# RASPILOTv1_1.net
KiCad netlist of a schematic drawn in EAGLE
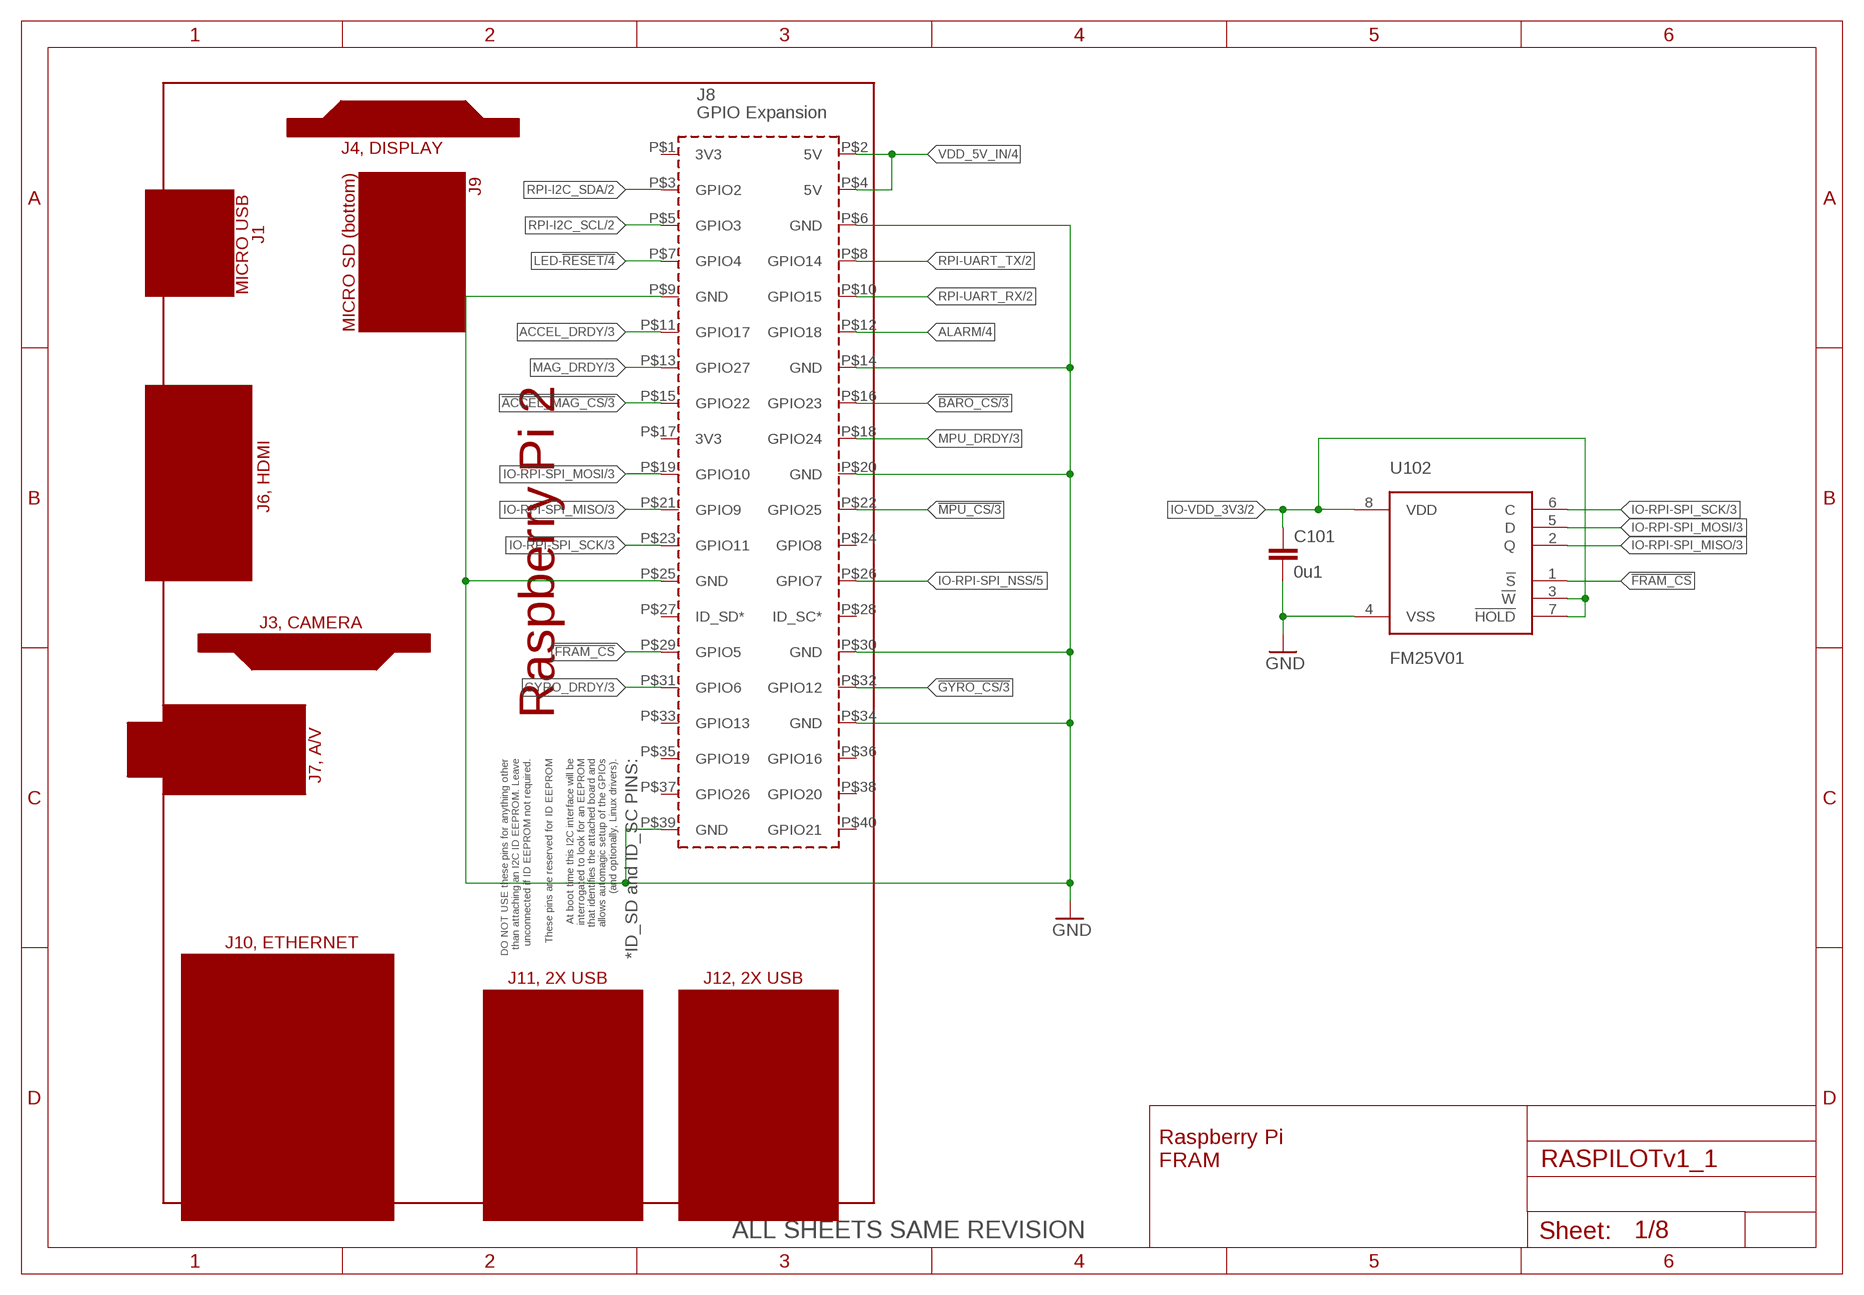
[diagram p0: schematic, sheet 1]
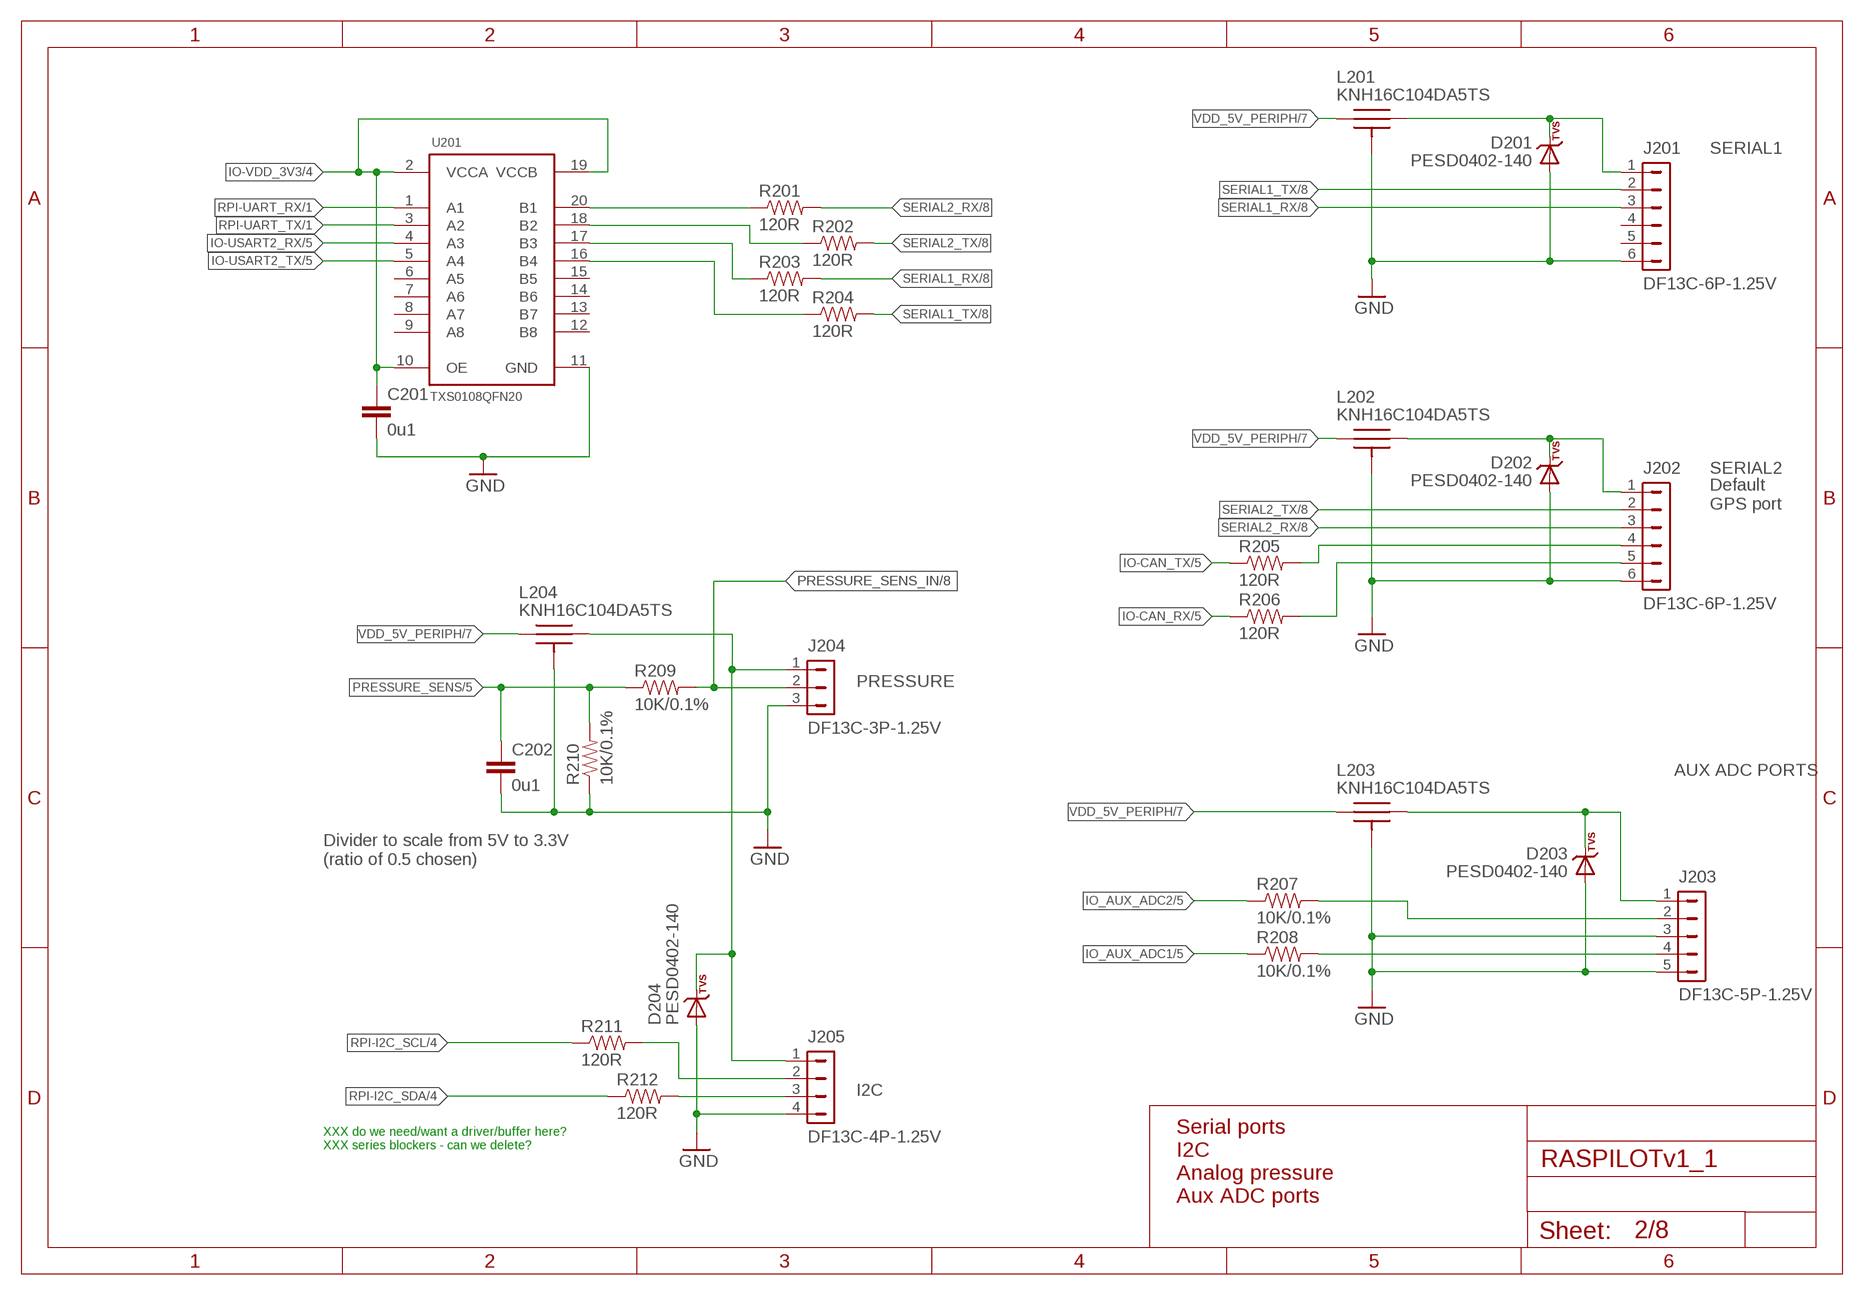
[diagram p1: schematic, sheet 2]
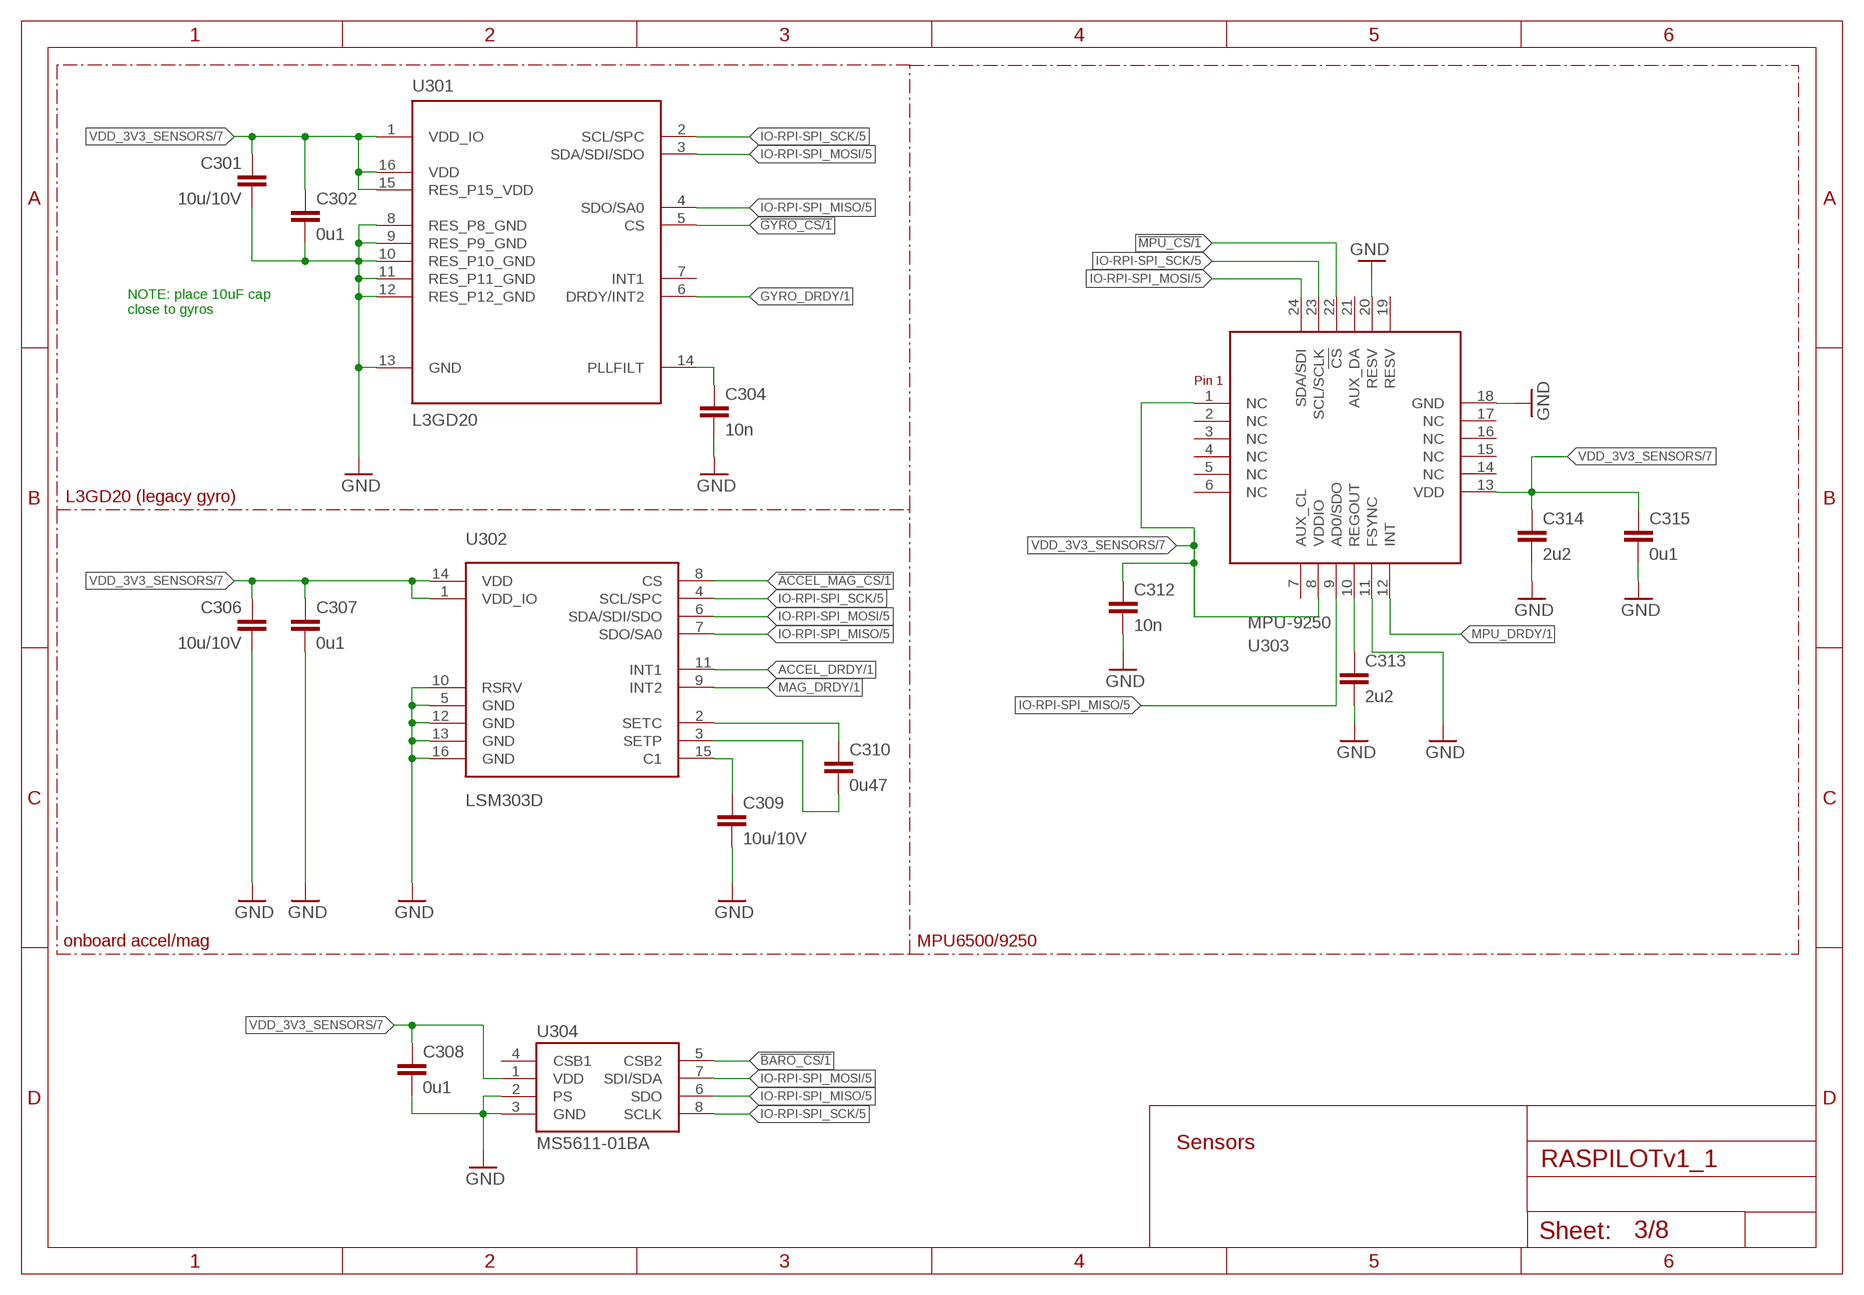
[diagram p2: schematic, sheet 3]
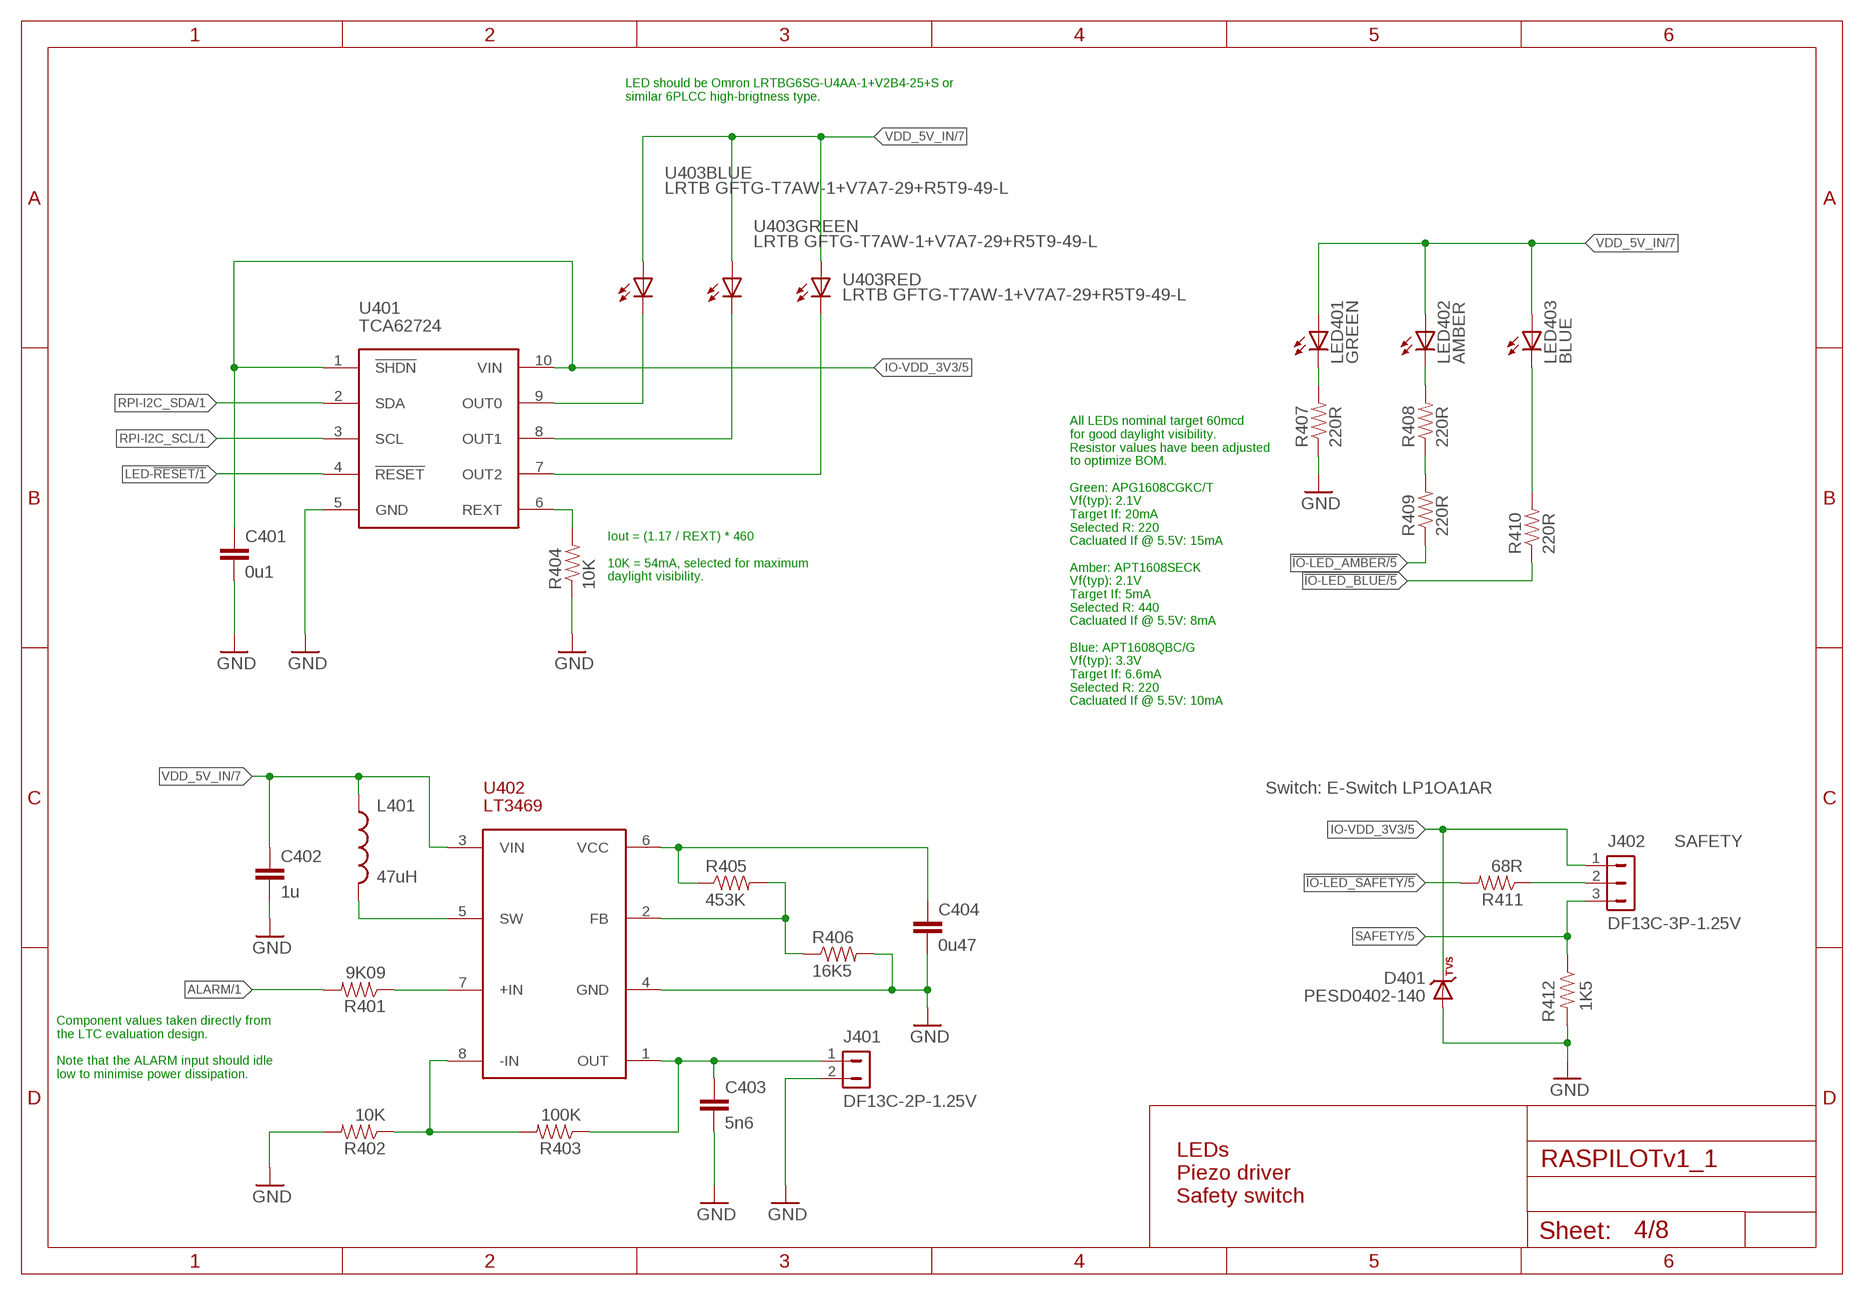
[diagram p3: schematic, sheet 4]
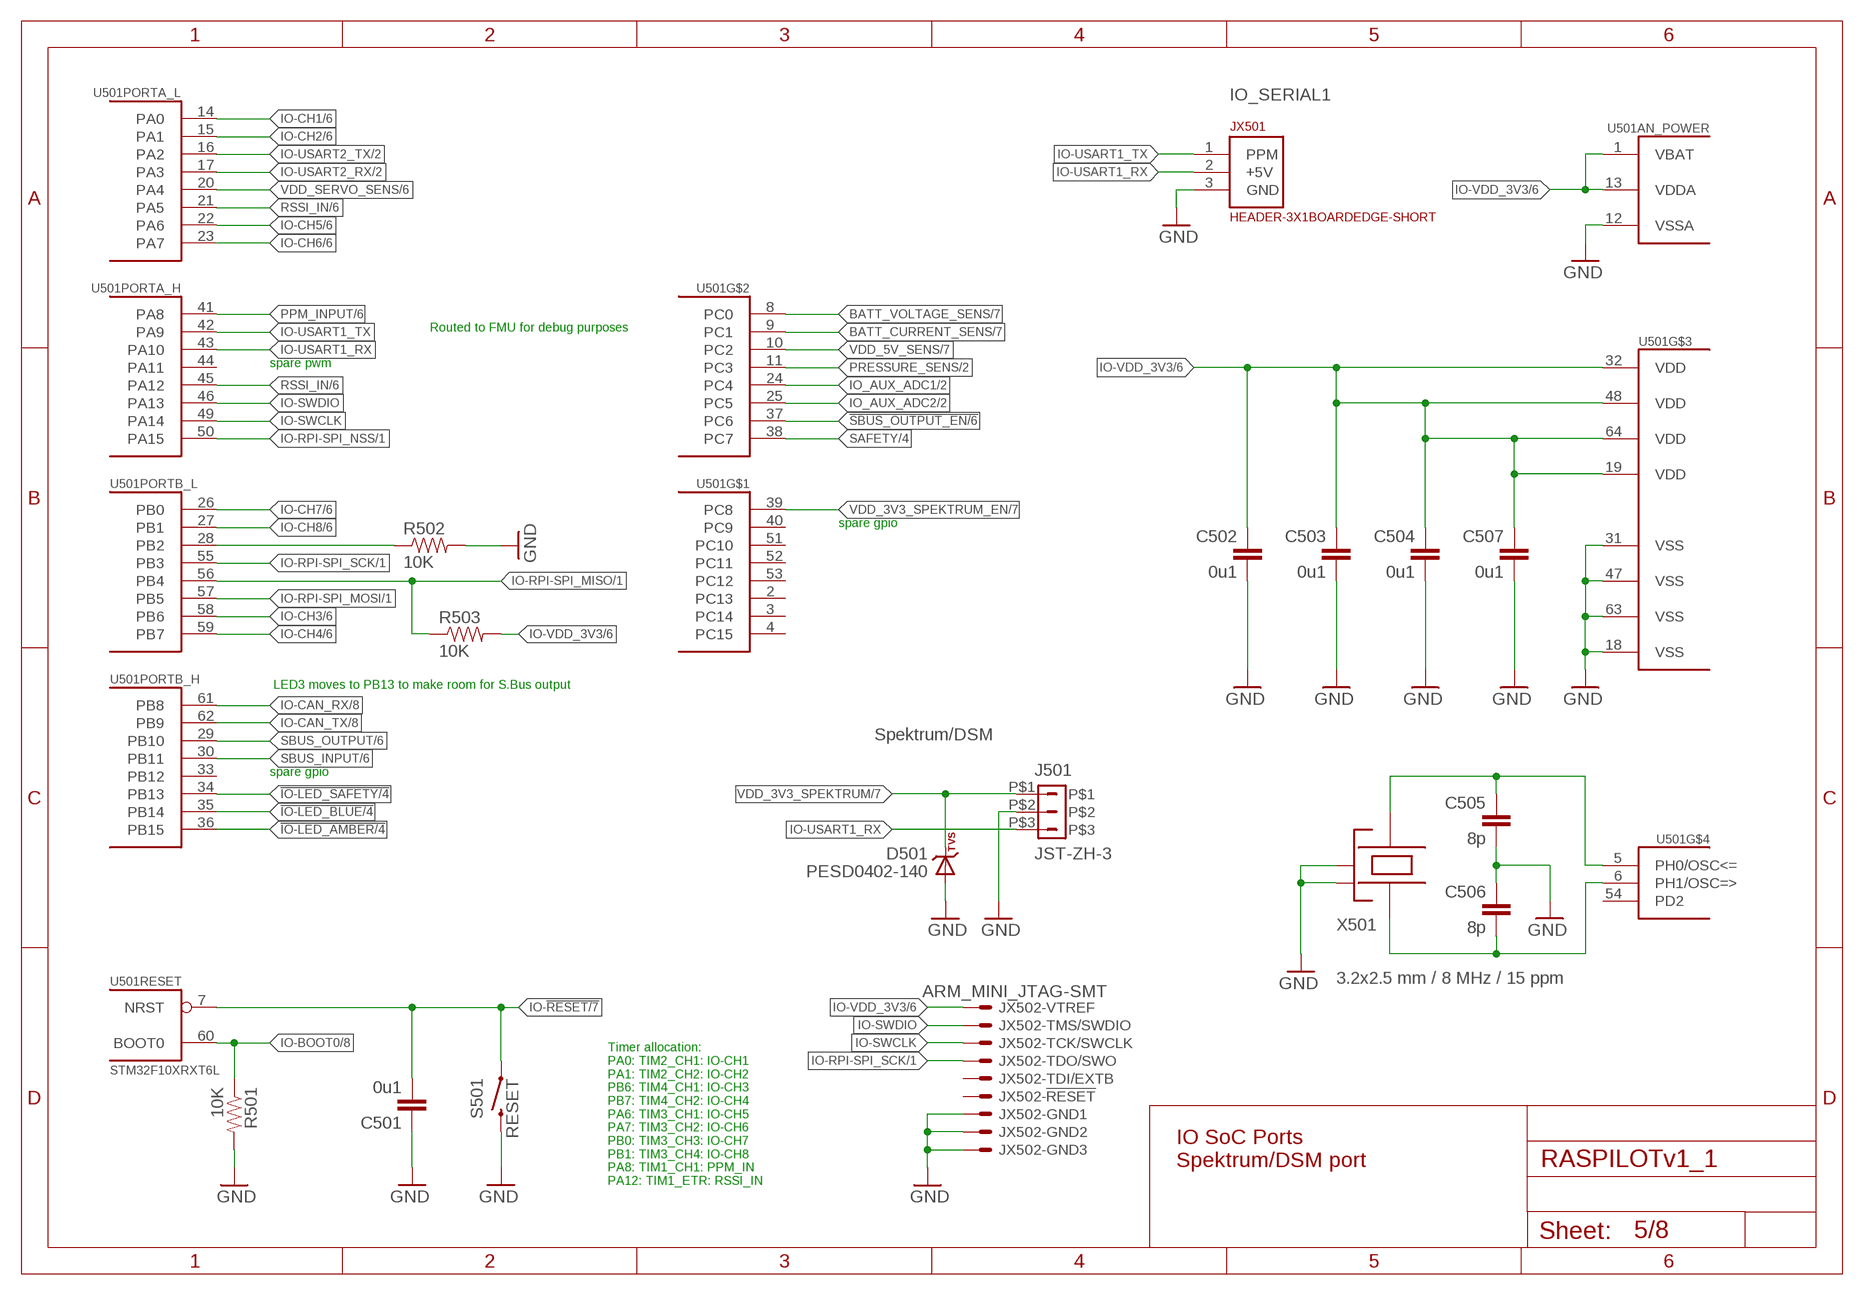
[diagram p4: schematic, sheet 5]
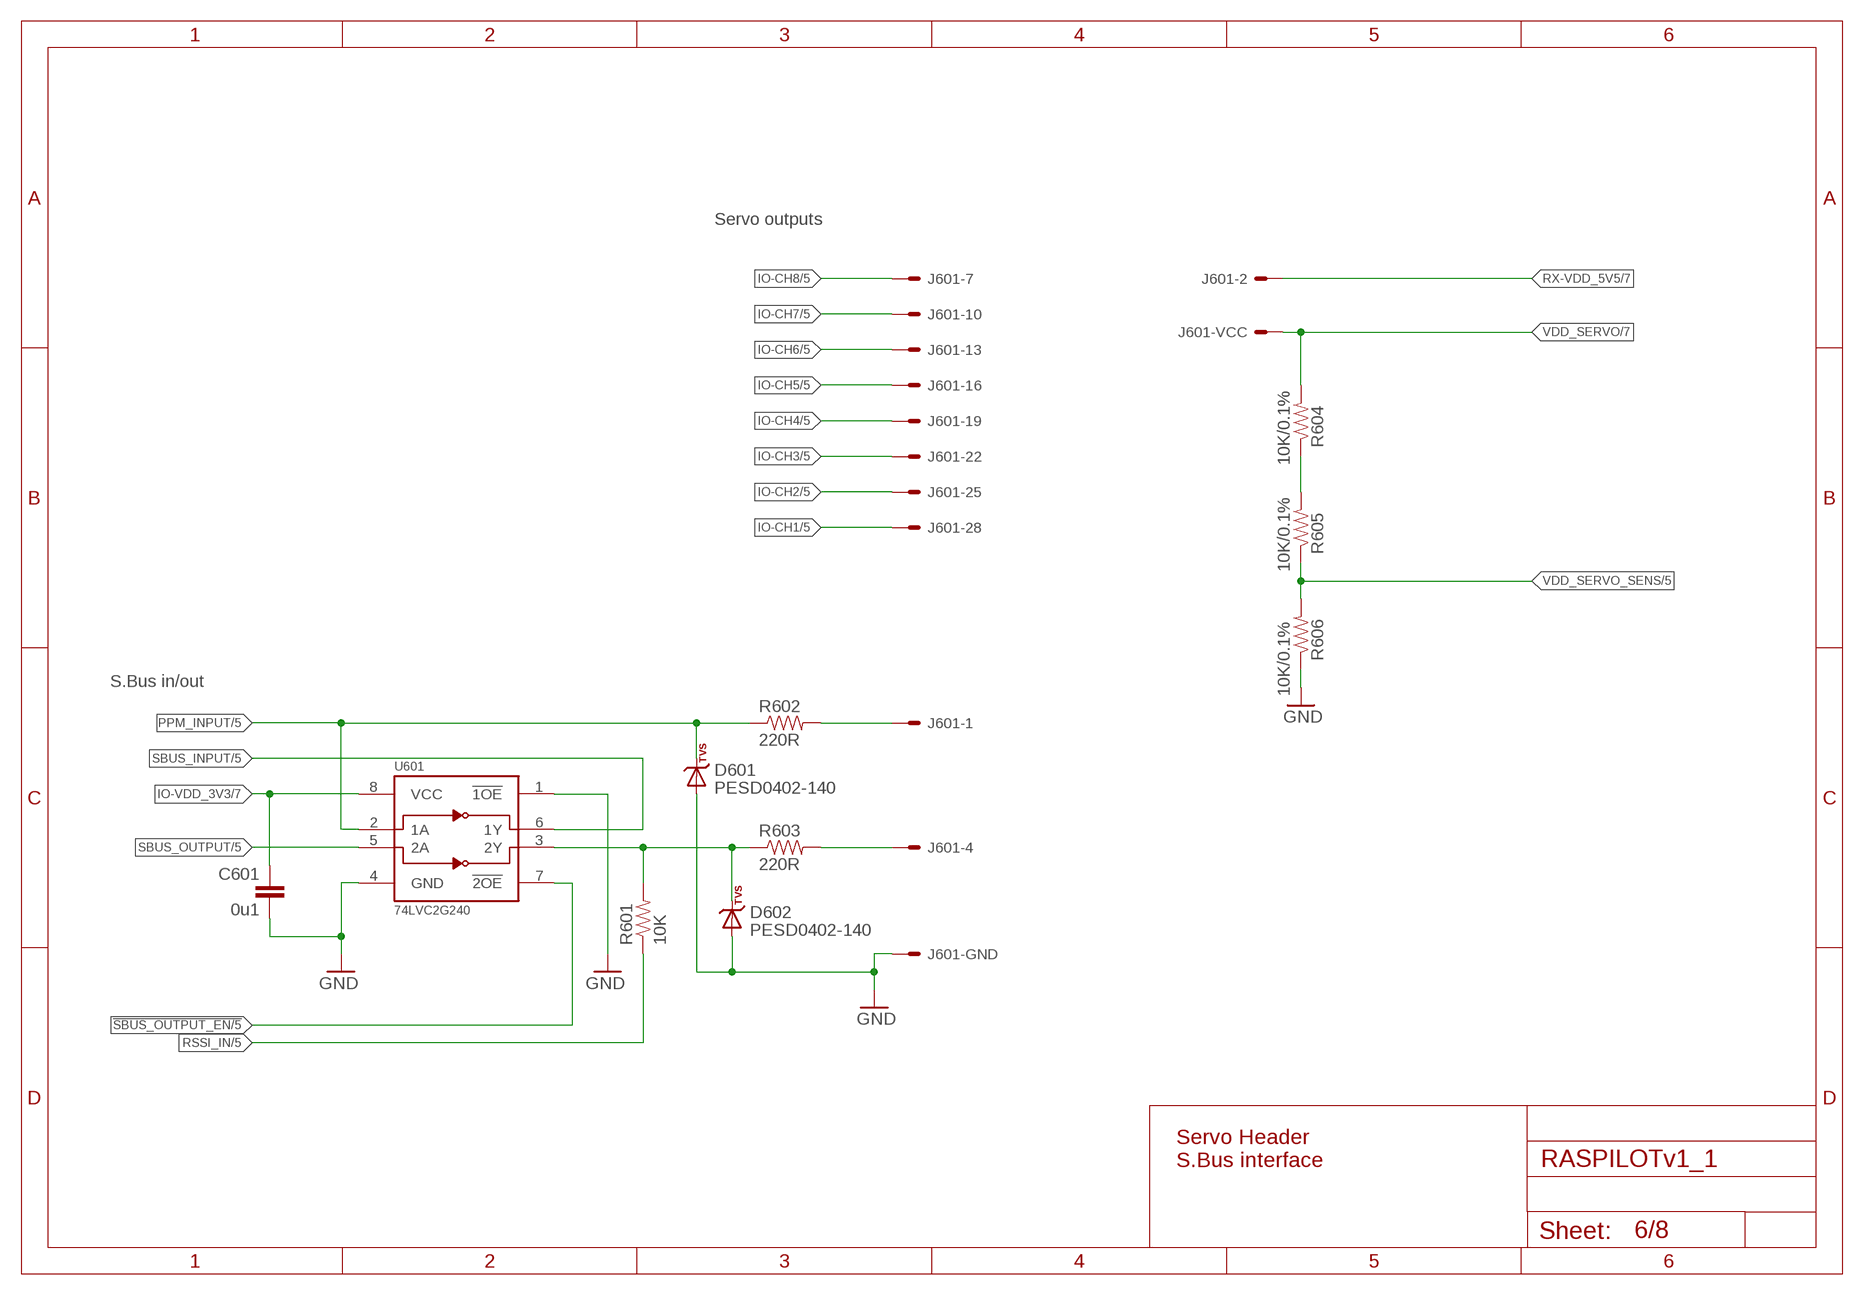
[diagram p5: schematic, sheet 6]
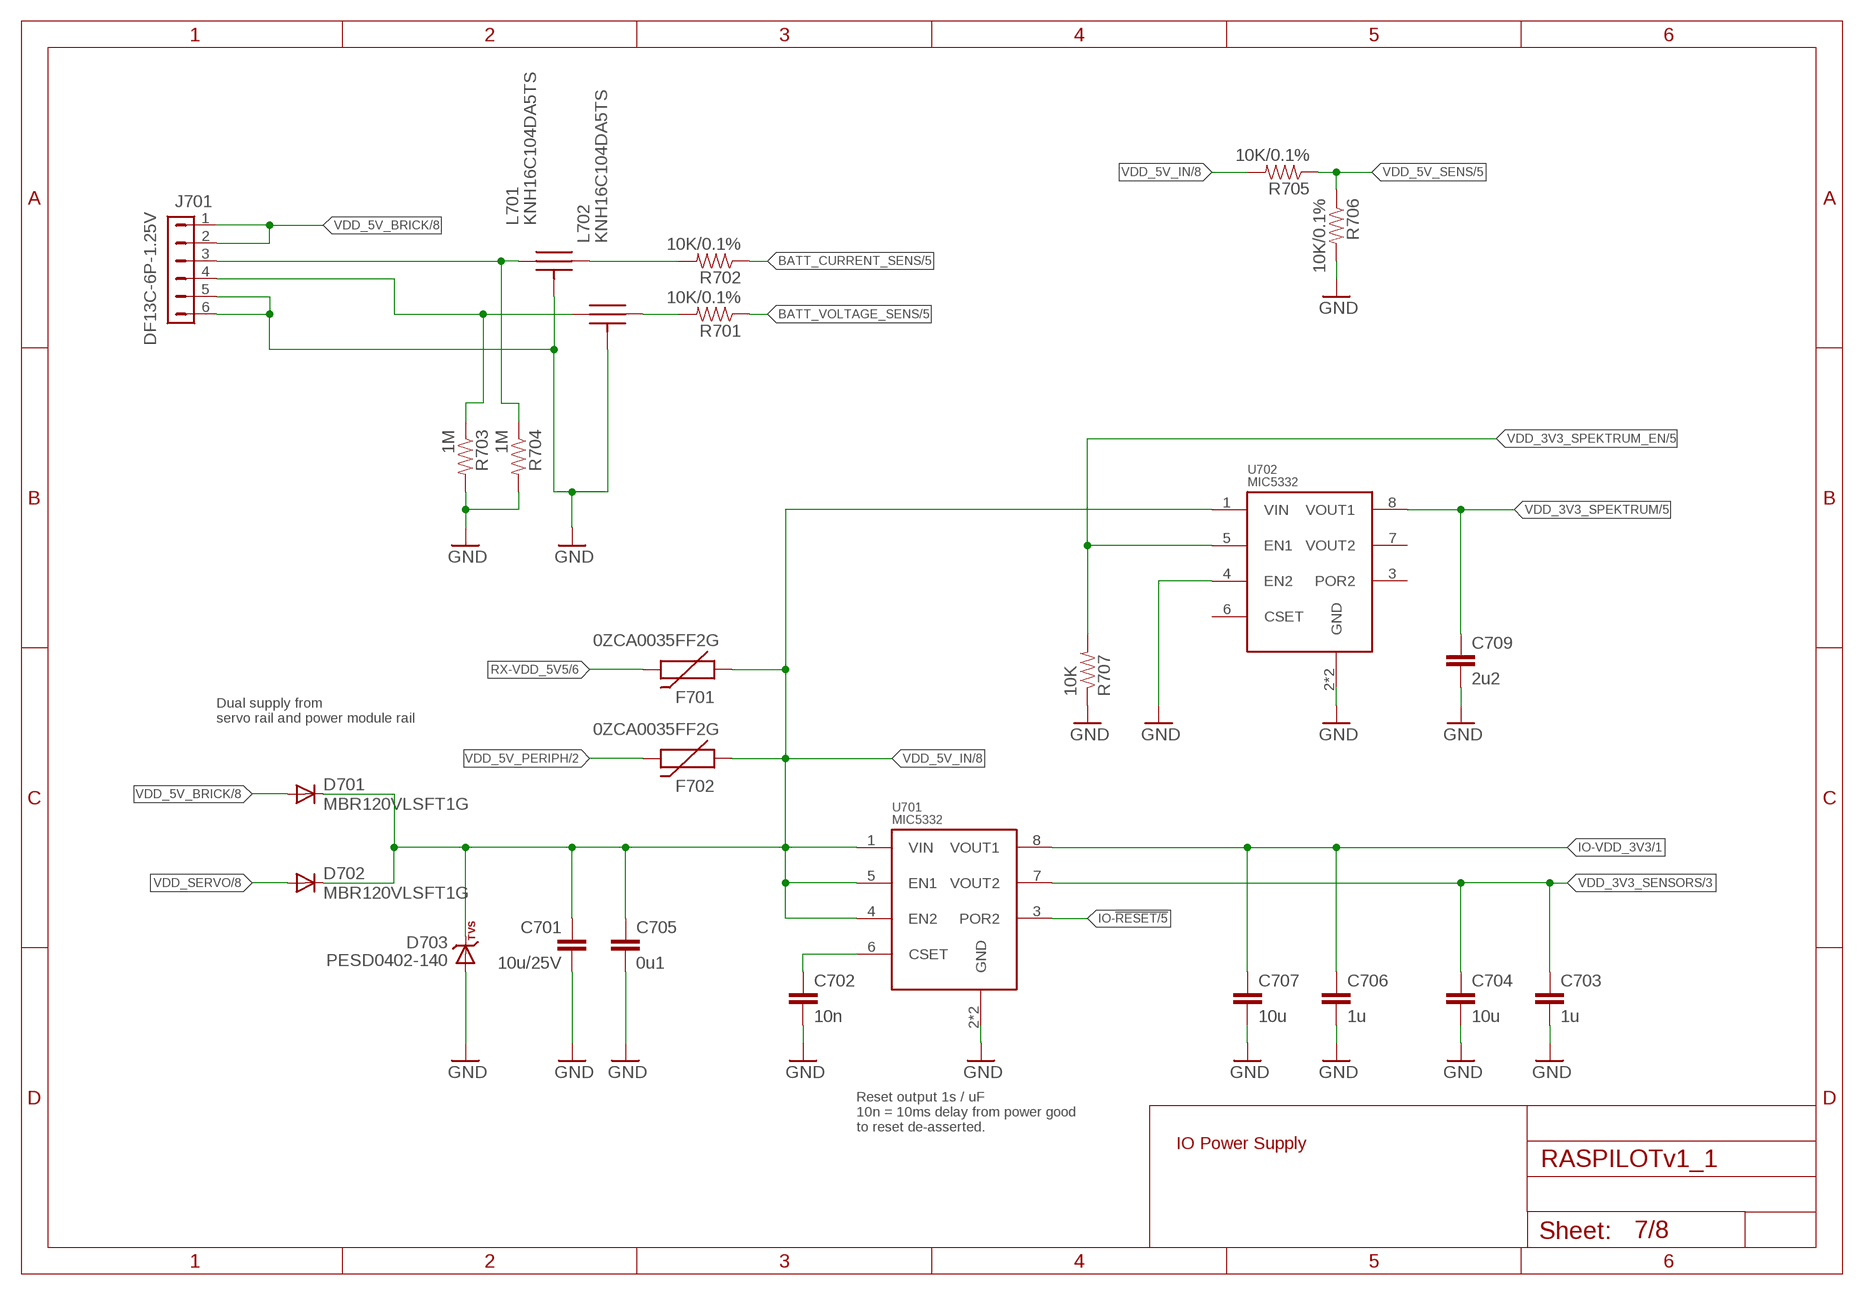
[diagram p6: schematic, sheet 7]
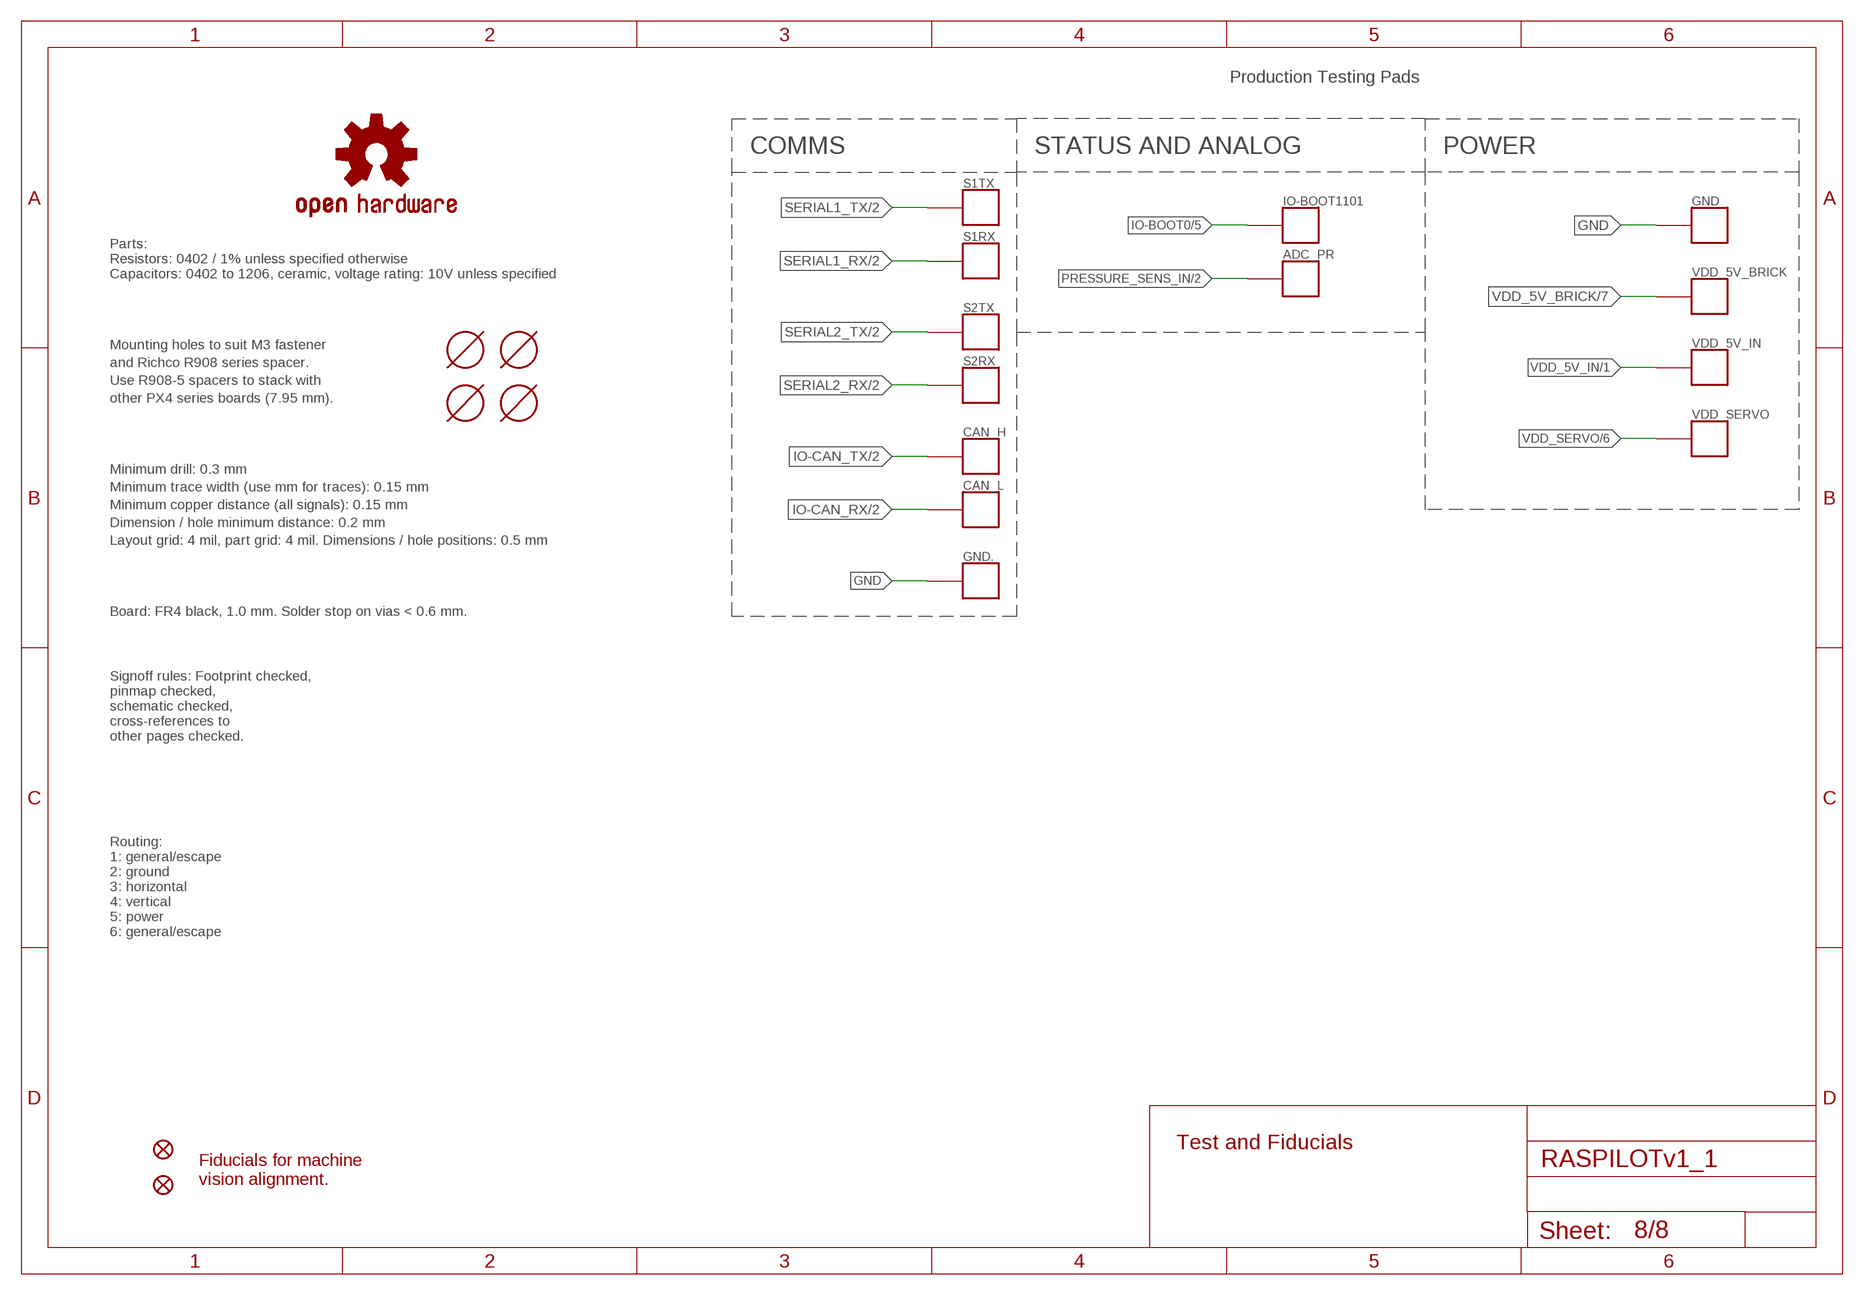
[diagram p7: schematic, sheet 8]

(export (version "E")
  (design (tool "Eeschema 10.0.6"))
  (components
    (comp (ref "C701")
      (value "10u/25V")
      (footprint "eagle-import:0805-CAP")
      (fields (field (name "PARTNO") "CL21A106KAYNNNE"))
      (libsource (lib "eagle-import") (part "CAP0805"))
    )
    (comp (ref "C702")
      (value "10n")
      (footprint "eagle-import:0402-CAP")
      (fields (field (name "PARTNO") "CC0402KRX7R7BB103"))
      (libsource (lib "eagle-import") (part "CAP0402"))
    )
    (comp (ref "C703")
      (value "1u")
      (footprint "eagle-import:0603-CAP")
      (fields (field (name "PARTNO") "CC0603ZRY5V7BB105"))
      (libsource (lib "eagle-import") (part "CAP0603"))
    )
    (comp (ref "C704")
      (value "10u")
      (footprint "eagle-import:0603-CAP")
      (fields (field (name "PARTNO") "C1608X5R1A106K080AC"))
      (libsource (lib "eagle-import") (part "CAP0603"))
    )
    (comp (ref "C705")
      (value "0u1")
      (footprint "eagle-import:0402-CAP")
      (fields (field (name "PARTNO") "CC0402ZRY5V7BB104"))
      (libsource (lib "eagle-import") (part "CAP0402"))
    )
    (comp (ref "C706")
      (value "1u")
      (footprint "eagle-import:0603-CAP")
      (fields (field (name "PARTNO") "CC0603ZRY5V7BB105"))
      (libsource (lib "eagle-import") (part "CAP0603"))
    )
    (comp (ref "C707")
      (value "10u")
      (footprint "eagle-import:0603-CAP")
      (fields (field (name "PARTNO") "C1608X5R1A106K080AC"))
      (libsource (lib "eagle-import") (part "CAP0603"))
    )
    (comp (ref "C709")
      (value "2u2")
      (footprint "eagle-import:0402-CAP")
      (fields (field (name "PARTNO") "C1005X6S1C225K050BC"))
      (libsource (lib "eagle-import") (part "CAP0402"))
    )
    (comp (ref "D701")
      (value "MBR120VLSFT1G")
      (footprint "eagle-import:SOD-123-DIO")
      (libsource (lib "eagle-import") (part "DIODE-SOD-123"))
    )
    (comp (ref "D702")
      (value "MBR120VLSFT1G")
      (footprint "eagle-import:SOD-123-DIO")
      (libsource (lib "eagle-import") (part "DIODE-SOD-123"))
    )
    (comp (ref "D703")
      (value "PESD0402-140")
      (footprint "eagle-import:0402-TVS")
      (libsource (lib "eagle-import") (part "DIODE-TVS"))
    )
    (comp (ref "F701")
      (value "0ZCA0035FF2G")
      (footprint "eagle-import:PTC-1206")
      (libsource (lib "eagle-import") (part "PTCSMD"))
    )
    (comp (ref "F702")
      (value "0ZCA0035FF2G")
      (footprint "eagle-import:PTC-1206")
      (libsource (lib "eagle-import") (part "PTCSMD"))
    )
    (comp (ref "J701")
      (value "DF13C-6P-1.25V")
      (footprint "eagle-import:DF13C-6P-1.25V")
      (fields (field (name "PARTNO") "DF13C-6P-1.25V(20)"))
      (libsource (lib "eagle-import") (part "DF13-6P-1.25V"))
    )
    (comp (ref "L701")
      (value "KNH16C104DA5TS")
      (footprint "eagle-import:KYOCERA-KNH16-DA")
      (libsource (lib "eagle-import") (part "KNH16C104DA5TS"))
    )
    (comp (ref "L702")
      (value "KNH16C104DA5TS")
      (footprint "eagle-import:KYOCERA-KNH16-DA")
      (libsource (lib "eagle-import") (part "KNH16C104DA5TS"))
    )
    (comp (ref "R701")
      (value "10K/0.1%")
      (footprint "eagle-import:0402-RES")
      (fields (field (name "PARTNO") "ERA-2AEB103X"))
      (libsource (lib "eagle-import") (part "RESISTOR0402-RES"))
    )
    (comp (ref "R702")
      (value "10K/0.1%")
      (footprint "eagle-import:0402-RES")
      (fields (field (name "PARTNO") "ERA-2AEB103X"))
      (libsource (lib "eagle-import") (part "RESISTOR0402-RES"))
    )
    (comp (ref "R703")
      (value "1M")
      (footprint "eagle-import:0402-RES")
      (fields (field (name "PARTNO") "RC0402FR-071ML"))
      (libsource (lib "eagle-import") (part "RESISTOR0402-RES"))
    )
    (comp (ref "R704")
      (value "1M")
      (footprint "eagle-import:0402-RES")
      (fields (field (name "PARTNO") "RC0402FR-071ML"))
      (libsource (lib "eagle-import") (part "RESISTOR0402-RES"))
    )
    (comp (ref "R705")
      (value "10K/0.1%")
      (footprint "eagle-import:0402-RES")
      (fields (field (name "PARTNO") "ERA-2AEB103X"))
      (libsource (lib "eagle-import") (part "RESISTOR0402-RES"))
    )
    (comp (ref "R706")
      (value "10K/0.1%")
      (footprint "eagle-import:0402-RES")
      (fields (field (name "PARTNO") "ERA-2AEB103X"))
      (libsource (lib "eagle-import") (part "RESISTOR0402-RES"))
    )
    (comp (ref "R707")
      (value "10K")
      (footprint "eagle-import:0402-RES")
      (fields (field (name "PARTNO") "RC0402FR-0710KL"))
      (libsource (lib "eagle-import") (part "RESISTOR0402-RES"))
    )
    (comp (ref "U701")
      (value "MIC5332")
      (footprint "eagle-import:MLF-8-EPAD")
      (fields (field (name "PARTNO") "MIC5332-SSYMT"))
      (libsource (lib "eagle-import") (part "MIC5332"))
    )
    (comp (ref "U702")
      (value "MIC5332")
      (footprint "eagle-import:MLF-8-EPAD")
      (fields (field (name "PARTNO") "MIC5332-SSYMT"))
      (libsource (lib "eagle-import") (part "MIC5332"))
    )
    (comp (ref "C301")
      (value "10u/10V")
      (footprint "eagle-import:0805-CAP")
      (fields (field (name "PARTNO") "CC0805ZKY5V6BB106"))
      (libsource (lib "eagle-import") (part "CAP0805"))
    )
    (comp (ref "C302")
      (value "0u1")
      (footprint "eagle-import:0402-CAP")
      (fields (field (name "PARTNO") "CC0402ZRY5V7BB104"))
      (libsource (lib "eagle-import") (part "CAP0402"))
    )
    (comp (ref "C304")
      (value "10n")
      (footprint "eagle-import:0402-CAP")
      (fields (field (name "PARTNO") "CC0402KRX7R7BB103"))
      (libsource (lib "eagle-import") (part "CAP0402"))
    )
    (comp (ref "C306")
      (value "10u/10V")
      (footprint "eagle-import:0805-CAP")
      (fields (field (name "PARTNO") "CC0805ZKY5V6BB106"))
      (libsource (lib "eagle-import") (part "CAP0805"))
    )
    (comp (ref "C307")
      (value "0u1")
      (footprint "eagle-import:0402-CAP")
      (fields (field (name "PARTNO") "CC0402ZRY5V7BB104"))
      (libsource (lib "eagle-import") (part "CAP0402"))
    )
    (comp (ref "C308")
      (value "0u1")
      (footprint "eagle-import:0402-CAP")
      (fields (field (name "PARTNO") "CC0402ZRY5V7BB104"))
      (libsource (lib "eagle-import") (part "CAP0402"))
    )
    (comp (ref "C309")
      (value "10u/10V")
      (footprint "eagle-import:0805-CAP")
      (fields (field (name "PARTNO") "CC0805ZKY5V6BB106"))
      (libsource (lib "eagle-import") (part "CAP0805"))
    )
    (comp (ref "C310")
      (value "0u47")
      (footprint "eagle-import:0402-CAP")
      (fields (field (name "PARTNO") "C1005X5R1C474K050BC"))
      (libsource (lib "eagle-import") (part "CAP0402"))
    )
    (comp (ref "C312")
      (value "10n")
      (footprint "eagle-import:0603-CAP")
      (fields (field (name "PARTNO") "C0603C103J5RAC7411"))
      (libsource (lib "eagle-import") (part "CAP0603"))
    )
    (comp (ref "C313")
      (value "2u2")
      (footprint "eagle-import:0603-CAP")
      (fields (field (name "PARTNO") "C1608X6S1C225K080AC"))
      (libsource (lib "eagle-import") (part "CAP0603"))
    )
    (comp (ref "C314")
      (value "2u2")
      (footprint "eagle-import:0603-CAP")
      (libsource (lib "eagle-import") (part "CAP0603"))
    )
    (comp (ref "C315")
      (value "0u1")
      (footprint "eagle-import:0402-CAP")
      (fields (field (name "PARTNO") "CC0402ZRY5V7BB104"))
      (libsource (lib "eagle-import") (part "CAP0402"))
    )
    (comp (ref "U301")
      (value "L3GD20")
      (footprint "eagle-import:L3G4200DH-MAN")
      (libsource (lib "eagle-import") (part "L3G4200DH-LL"))
    )
    (comp (ref "U302")
      (value "LSM303D")
      (footprint "eagle-import:LGA-16L")
      (libsource (lib "eagle-import") (part "LSM303D"))
    )
    (comp (ref "U303")
      (value "MPU-9250")
      (footprint "eagle-import:MPU-6500")
      (libsource (lib "eagle-import") (part "MPU-6500"))
    )
    (comp (ref "U304")
      (value "MS5611-01BA")
      (footprint "eagle-import:MS5611-01BA")
      (libsource (lib "eagle-import") (part "MS5611-01BA"))
    )
    (comp (ref "C401")
      (value "0u1")
      (footprint "eagle-import:0402-CAP")
      (fields (field (name "PARTNO") "CC0402ZRY5V7BB104"))
      (libsource (lib "eagle-import") (part "CAP0402"))
    )
    (comp (ref "C402")
      (value "1u")
      (footprint "eagle-import:0603-CAP")
      (fields (field (name "PARTNO") "CC0603ZRY5V7BB105"))
      (libsource (lib "eagle-import") (part "CAP0603"))
    )
    (comp (ref "C403")
      (value "5n6")
      (footprint "eagle-import:0402-CAP")
      (fields (field (name "PARTNO") "C0402C562K5RACTU"))
      (libsource (lib "eagle-import") (part "CAP0402"))
    )
    (comp (ref "C404")
      (value "0u47")
      (footprint "eagle-import:0402-CAP")
      (fields (field (name "PARTNO") "C1005X5R1C474K050BC"))
      (libsource (lib "eagle-import") (part "CAP0402"))
    )
    (comp (ref "D401")
      (value "PESD0402-140")
      (footprint "eagle-import:0402-TVS")
      (libsource (lib "eagle-import") (part "DIODE-TVS"))
    )
    (comp (ref "J401")
      (value "DF13C-2P-1.25V")
      (footprint "eagle-import:DF13C-2P-1.25V")
      (fields (field (name "PARTNO") "DF13C-2P-1.25V(20)"))
      (libsource (lib "eagle-import") (part "DF13-2P-1.25V"))
    )
    (comp (ref "J402")
      (value "DF13C-3P-1.25V")
      (footprint "eagle-import:DF13C-3P-1.25V")
      (fields (field (name "PARTNO") "DF13C-3P-1.25V(20)"))
      (libsource (lib "eagle-import") (part "DF13-3P-1.25V"))
    )
    (comp (ref "L401")
      (value "47uH")
      (footprint "eagle-import:0805-IND")
      (fields (field (name "PARTNO") "MLZ2012M470W"))
      (libsource (lib "eagle-import") (part "INDUCTOR0805"))
    )
    (comp (ref "LED401")
      (value "GREEN")
      (footprint "eagle-import:0603-LED")
      (fields (field (name "PARTNO") "APTD1608CGCK"))
      (libsource (lib "eagle-import") (part "LED0603"))
    )
    (comp (ref "LED402")
      (value "AMBER")
      (footprint "eagle-import:0603-LED")
      (fields (field (name "PARTNO") "APTD1608SECK"))
      (libsource (lib "eagle-import") (part "LED0603"))
    )
    (comp (ref "LED403")
      (value "BLUE")
      (footprint "eagle-import:0603-LED")
      (fields (field (name "PARTNO") "APTD1608QBC/D"))
      (libsource (lib "eagle-import") (part "LED0603"))
    )
    (comp (ref "R401")
      (value "9K09")
      (footprint "eagle-import:0402-RES")
      (fields (field (name "PARTNO") "RMCF0402FT9K09"))
      (libsource (lib "eagle-import") (part "RESISTOR0402-RES"))
    )
    (comp (ref "R402")
      (value "10K")
      (footprint "eagle-import:0402-RES")
      (fields (field (name "PARTNO") "RC0402FR-0710KL"))
      (libsource (lib "eagle-import") (part "RESISTOR0402-RES"))
    )
    (comp (ref "R403")
      (value "100K")
      (footprint "eagle-import:0402-RES")
      (fields (field (name "PARTNO") "RC0402FR-07100KL"))
      (libsource (lib "eagle-import") (part "RESISTOR0402-RES"))
    )
    (comp (ref "R404")
      (value "10K")
      (footprint "eagle-import:0402-RES")
      (fields (field (name "PARTNO") "RC0402FR-0710KL"))
      (libsource (lib "eagle-import") (part "RESISTOR0402-RES"))
    )
    (comp (ref "R405")
      (value "453K")
      (footprint "eagle-import:0402-RES")
      (fields (field (name "PARTNO") "RMCF0402FT453K"))
      (libsource (lib "eagle-import") (part "RESISTOR0402-RES"))
    )
    (comp (ref "R406")
      (value "16K5")
      (footprint "eagle-import:0402-RES")
      (fields (field (name "PARTNO") "RMCF0402FT16K5"))
      (libsource (lib "eagle-import") (part "RESISTOR0402-RES"))
    )
    (comp (ref "R407")
      (value "220R")
      (footprint "eagle-import:0402-RES")
      (fields (field (name "PARTNO") "RC0402FR-07220RL"))
      (libsource (lib "eagle-import") (part "RESISTOR0402-RES"))
    )
    (comp (ref "R408")
      (value "220R")
      (footprint "eagle-import:0402-RES")
      (fields (field (name "PARTNO") "RC0402FR-07220RL"))
      (libsource (lib "eagle-import") (part "RESISTOR0402-RES"))
    )
    (comp (ref "R409")
      (value "220R")
      (footprint "eagle-import:0402-RES")
      (fields (field (name "PARTNO") "RC0402FR-07220RL"))
      (libsource (lib "eagle-import") (part "RESISTOR0402-RES"))
    )
    (comp (ref "R410")
      (value "220R")
      (footprint "eagle-import:0402-RES")
      (fields (field (name "PARTNO") "RC0402FR-07220RL"))
      (libsource (lib "eagle-import") (part "RESISTOR0402-RES"))
    )
    (comp (ref "R411")
      (value "68R")
      (footprint "eagle-import:0402-RES")
      (fields (field (name "PARTNO") "ERJ-2GEJ680X"))
      (libsource (lib "eagle-import") (part "RESISTOR0402-RES"))
    )
    (comp (ref "R412")
      (value "1K5")
      (footprint "eagle-import:0402-RES")
      (fields (field (name "PARTNO") "RC0402FR-071K5L"))
      (libsource (lib "eagle-import") (part "RESISTOR0402-RES"))
    )
    (comp (ref "U401")
      (value "TCA62724FMG")
      (footprint "eagle-import:SON10")
      (libsource (lib "eagle-import") (part "TCA62724FMG"))
    )
    (comp (ref "U402")
      (value "LT3469")
      (footprint "eagle-import:SOT23-8")
      (fields (field (name "PARTNO") "LT3469ETS8"))
      (libsource (lib "eagle-import") (part "LT3469"))
    )
    (comp (ref "U403")
      (value "LRTB GFTG-T7AW-1+V7A7-29+R5T9-49-L")
      (footprint "eagle-import:6-PLCC")
      (fields (field (name "PARTNO") "LRTB GFTG-T7AW-1+V7A7-29+R5T9-49-L"))
      (libsource (lib "eagle-import") (part "RGB-LED6-PLCC"))
    )
    (comp (ref "ADC_PR")
      (value "PAD.04")
      (footprint "eagle-import:PAD.04X.04")
      (libsource (lib "eagle-import") (part "PAD.04"))
    )
    (comp (ref "CAN_H")
      (value "PAD.04")
      (footprint "eagle-import:PAD.04X.04")
      (libsource (lib "eagle-import") (part "PAD.04"))
    )
    (comp (ref "CAN_L")
      (value "PAD.04")
      (footprint "eagle-import:PAD.04X.04")
      (libsource (lib "eagle-import") (part "PAD.04"))
    )
    (comp (ref "GND")
      (value "PAD.04")
      (footprint "eagle-import:PAD.04X.04")
      (libsource (lib "eagle-import") (part "PAD.04"))
    )
    (comp (ref "GND.")
      (value "PAD.04")
      (footprint "eagle-import:PAD.04X.04")
      (libsource (lib "eagle-import") (part "PAD.04"))
    )
    (comp (ref "IO-BOOT1101")
      (value "PAD.04")
      (footprint "eagle-import:PAD.04X.04")
      (libsource (lib "eagle-import") (part "PAD.04"))
    )
    (comp (ref "JP1")
      (value "FIDUCIAL1.5X3")
      (footprint "eagle-import:FIDUCIAL-1.5X3")
      (libsource (lib "eagle-import") (part "FIDUCIAL1.5X3"))
    )
    (comp (ref "JP2")
      (value "FIDUCIAL1.5X3")
      (footprint "eagle-import:FIDUCIAL-1.5X3")
      (libsource (lib "eagle-import") (part "FIDUCIAL1.5X3"))
    )
    (comp (ref "M3_MOUNT1101")
      (value "MOUNT-HOLE3.1MM")
      (footprint "eagle-import:MOUNT-HOLE3.1")
      (libsource (lib "eagle-import") (part "MOUNT-HOLE3.1MM"))
    )
    (comp (ref "M3_MOUNT1102")
      (value "MOUNT-HOLE3.1MM")
      (footprint "eagle-import:MOUNT-HOLE3.1")
      (libsource (lib "eagle-import") (part "MOUNT-HOLE3.1MM"))
    )
    (comp (ref "M3_MOUNT1103")
      (value "MOUNT-HOLE3.1MM")
      (footprint "eagle-import:MOUNT-HOLE3.1")
      (libsource (lib "eagle-import") (part "MOUNT-HOLE3.1MM"))
    )
    (comp (ref "M3_MOUNT1104")
      (value "MOUNT-HOLE3.1MM")
      (footprint "eagle-import:MOUNT-HOLE3.1")
      (libsource (lib "eagle-import") (part "MOUNT-HOLE3.1MM"))
    )
    (comp (ref "OSHW_LOGO")
      (value "OSHW-LOGOS")
      (footprint "eagle-import:OSHW-LOGO-S")
      (libsource (lib "eagle-import") (part "OSHW-LOGOS"))
    )
    (comp (ref "S1RX")
      (value "PAD.04")
      (footprint "eagle-import:PAD.04X.04")
      (libsource (lib "eagle-import") (part "PAD.04"))
    )
    (comp (ref "S1TX")
      (value "PAD.04")
      (footprint "eagle-import:PAD.04X.04")
      (libsource (lib "eagle-import") (part "PAD.04"))
    )
    (comp (ref "S2RX")
      (value "PAD.04")
      (footprint "eagle-import:PAD.04X.04")
      (libsource (lib "eagle-import") (part "PAD.04"))
    )
    (comp (ref "S2TX")
      (value "PAD.04")
      (footprint "eagle-import:PAD.04X.04")
      (libsource (lib "eagle-import") (part "PAD.04"))
    )
    (comp (ref "VDD_5V_BRICK")
      (value "PAD.04")
      (footprint "eagle-import:PAD.04X.04")
      (libsource (lib "eagle-import") (part "PAD.04"))
    )
    (comp (ref "VDD_5V_IN")
      (value "PAD.04")
      (footprint "eagle-import:PAD.04X.04")
      (libsource (lib "eagle-import") (part "PAD.04"))
    )
    (comp (ref "VDD_SERVO")
      (value "PAD.04")
      (footprint "eagle-import:PAD.04X.04")
      (libsource (lib "eagle-import") (part "PAD.04"))
    )
    (comp (ref "C601")
      (value "0u1")
      (footprint "eagle-import:0402-CAP")
      (fields (field (name "PARTNO") "CC0402ZRY5V7BB104"))
      (libsource (lib "eagle-import") (part "CAP0402"))
    )
    (comp (ref "D601")
      (value "PESD0402-140")
      (footprint "eagle-import:0402-TVS")
      (libsource (lib "eagle-import") (part "DIODE-TVS"))
    )
    (comp (ref "D602")
      (value "PESD0402-140")
      (footprint "eagle-import:0402-TVS")
      (libsource (lib "eagle-import") (part "DIODE-TVS"))
    )
    (comp (ref "J601")
      (value "HEADER-3X10")
      (footprint "eagle-import:3X10RA")
      (libsource (lib "eagle-import") (part "HEADER-3X10"))
    )
    (comp (ref "R601")
      (value "10K")
      (footprint "eagle-import:0402-RES")
      (fields (field (name "PARTNO") "RC0402FR-0710KL"))
      (libsource (lib "eagle-import") (part "RESISTOR0402-RES"))
    )
    (comp (ref "R602")
      (value "220R")
      (footprint "eagle-import:0402-RES")
      (fields (field (name "PARTNO") "RC0402FR-07220RL"))
      (libsource (lib "eagle-import") (part "RESISTOR0402-RES"))
    )
    (comp (ref "R603")
      (value "220R")
      (footprint "eagle-import:0402-RES")
      (fields (field (name "PARTNO") "RC0402FR-07220RL"))
      (libsource (lib "eagle-import") (part "RESISTOR0402-RES"))
    )
    (comp (ref "R604")
      (value "10K/0.1%")
      (footprint "eagle-import:0402-RES")
      (fields (field (name "PARTNO") "ERA-2AEB103X"))
      (libsource (lib "eagle-import") (part "RESISTOR0402-RES"))
    )
    (comp (ref "R605")
      (value "10K/0.1%")
      (footprint "eagle-import:0402-RES")
      (fields (field (name "PARTNO") "ERA-2AEB103X"))
      (libsource (lib "eagle-import") (part "RESISTOR0402-RES"))
    )
    (comp (ref "R606")
      (value "10K/0.1%")
      (footprint "eagle-import:0402-RES")
      (fields (field (name "PARTNO") "ERA-2AEB103X"))
      (libsource (lib "eagle-import") (part "RESISTOR0402-RES"))
    )
    (comp (ref "U601")
      (value "74LVC2G240")
      (footprint "eagle-import:TSSOP8_SOT505-2")
      (fields (field (name "PARTNO") "74LVC2G240DP,125"))
      (libsource (lib "eagle-import") (part "74LVC2G240-TSSOP-8"))
    )
    (comp (ref "C101")
      (value "0u1")
      (footprint "eagle-import:0402-CAP")
      (fields (field (name "PARTNO") "CC0402ZRY5V7BB104"))
      (libsource (lib "eagle-import") (part "CAP0402"))
    )
    (comp (ref "U101")
      (value "RPI2")
      (footprint "eagle-import:RPI2")
      (libsource (lib "eagle-import") (part "RPI2"))
    )
    (comp (ref "U102")
      (value "FM25V01")
      (footprint "eagle-import:SO08")
      (fields (field (name "PARTNO") "FM25V01-G"))
      (libsource (lib "eagle-import") (part "FM25V01"))
    )
    (comp (ref "C501")
      (value "0u1")
      (footprint "eagle-import:0402-CAP")
      (fields (field (name "PARTNO") "CC0402ZRY5V7BB104"))
      (libsource (lib "eagle-import") (part "CAP0402"))
    )
    (comp (ref "C502")
      (value "0u1")
      (footprint "eagle-import:0402-CAP")
      (fields (field (name "PARTNO") "CC0402ZRY5V7BB104"))
      (libsource (lib "eagle-import") (part "CAP0402"))
    )
    (comp (ref "C503")
      (value "0u1")
      (footprint "eagle-import:0402-CAP")
      (fields (field (name "PARTNO") "CC0402ZRY5V7BB104"))
      (libsource (lib "eagle-import") (part "CAP0402"))
    )
    (comp (ref "C504")
      (value "0u1")
      (footprint "eagle-import:0402-CAP")
      (fields (field (name "PARTNO") "CC0402ZRY5V7BB104"))
      (libsource (lib "eagle-import") (part "CAP0402"))
    )
    (comp (ref "C505")
      (value "8p")
      (footprint "eagle-import:0402-CAP")
      (fields (field (name "PARTNO") "C1005C0G1H080C"))
      (libsource (lib "eagle-import") (part "CAP0402"))
    )
    (comp (ref "C506")
      (value "8p")
      (footprint "eagle-import:0402-CAP")
      (fields (field (name "PARTNO") "C1005C0G1H080C"))
      (libsource (lib "eagle-import") (part "CAP0402"))
    )
    (comp (ref "C507")
      (value "0u1")
      (footprint "eagle-import:0402-CAP")
      (fields (field (name "PARTNO") "CC0402ZRY5V7BB104"))
      (libsource (lib "eagle-import") (part "CAP0402"))
    )
    (comp (ref "D501")
      (value "PESD0402-140")
      (footprint "eagle-import:0402-TVS")
      (libsource (lib "eagle-import") (part "DIODE-TVS"))
    )
    (comp (ref "J501")
      (value "JST-ZH-3")
      (footprint "eagle-import:JST-ZH-SMT-VERTICAL")
      (fields (field (name "PARTNO") "B3B-ZR-SM4-TF (LF)(SN)(P)"))
      (libsource (lib "eagle-import") (part "JST-ZH-3"))
    )
    (comp (ref "JX501")
      (value "HEADER-3X1BOARDEDGE-SHORT")
      (footprint "eagle-import:HEADER_3X01_SMD_H_BOARD_EDGE_SHORT")
      (libsource (lib "eagle-import") (part "HEADER-3X1BOARDEDGE-SHORT"))
    )
    (comp (ref "JX502")
      (value "ARM_MINI_JTAG-SMT")
      (footprint "eagle-import:FTSH-105-01-XXX-DV-K")
      (fields (field (name "BOM") "EXCLUDE") (field (name "PARTNO") "M50-3900542"))
      (libsource (lib "eagle-import") (part "ARM_MINI_JTAG-SMT"))
    )
    (comp (ref "R501")
      (value "10K")
      (footprint "eagle-import:0402-RES")
      (fields (field (name "PARTNO") "RC0402FR-0710KL"))
      (libsource (lib "eagle-import") (part "RESISTOR0402-RES"))
    )
    (comp (ref "R502")
      (value "10K")
      (footprint "eagle-import:0402-RES")
      (fields (field (name "PARTNO") "RC0402FR-0710KL"))
      (libsource (lib "eagle-import") (part "RESISTOR0402-RES"))
    )
    (comp (ref "R503")
      (value "10K")
      (footprint "eagle-import:0402-RES")
      (fields (field (name "PARTNO") "RC0402FR-0710KL"))
      (libsource (lib "eagle-import") (part "RESISTOR0402-RES"))
    )
    (comp (ref "S501")
      (value "RESET")
      (footprint "eagle-import:EVQP7J01K")
      (fields (field (name "PARTNO") "EVQ-P7J01P"))
      (libsource (lib "eagle-import") (part "SWITCH-MOMENTARY-2"))
    )
    (comp (ref "U501")
      (value "STM32F10XRXT6L")
      (footprint "eagle-import:TQFP64")
      (libsource (lib "eagle-import") (part "STM32F10XRXT6L"))
    )
    (comp (ref "X501")
      (value "3.2x2.5 mm / 8 MHz / 15 ppm")
      (footprint "eagle-import:OSCILLATOR-3.2X2.5")
      (fields (field (name "PARTNO") "NX3225SA-24.000000MHZ"))
      (libsource (lib "eagle-import") (part "OSCILLATOR-3.2X2.5"))
    )
    (comp (ref "C201")
      (value "0u1")
      (footprint "eagle-import:0402-CAP")
      (fields (field (name "PARTNO") "CC0402ZRY5V7BB104"))
      (libsource (lib "eagle-import") (part "CAP0402"))
    )
    (comp (ref "C202")
      (value "0u1")
      (footprint "eagle-import:0402-CAP")
      (fields (field (name "PARTNO") "CC0402ZRY5V7BB104"))
      (libsource (lib "eagle-import") (part "CAP0402"))
    )
    (comp (ref "D201")
      (value "PESD0402-140")
      (footprint "eagle-import:0402-TVS")
      (libsource (lib "eagle-import") (part "DIODE-TVS"))
    )
    (comp (ref "D202")
      (value "PESD0402-140")
      (footprint "eagle-import:0402-TVS")
      (libsource (lib "eagle-import") (part "DIODE-TVS"))
    )
    (comp (ref "D203")
      (value "PESD0402-140")
      (footprint "eagle-import:0402-TVS")
      (libsource (lib "eagle-import") (part "DIODE-TVS"))
    )
    (comp (ref "D204")
      (value "PESD0402-140")
      (footprint "eagle-import:0402-TVS")
      (libsource (lib "eagle-import") (part "DIODE-TVS"))
    )
    (comp (ref "J201")
      (value "DF13C-6P-1.25V")
      (footprint "eagle-import:DF13C-6P-1.25V")
      (fields (field (name "PARTNO") "DF13C-6P-1.25V(20)"))
      (libsource (lib "eagle-import") (part "DF13-6P-1.25V"))
    )
    (comp (ref "J202")
      (value "DF13C-6P-1.25V")
      (footprint "eagle-import:DF13C-6P-1.25V")
      (fields (field (name "PARTNO") "DF13C-6P-1.25V(20)"))
      (libsource (lib "eagle-import") (part "DF13-6P-1.25V"))
    )
    (comp (ref "J203")
      (value "DF13C-5P-1.25V")
      (footprint "eagle-import:DF13C-5P-1.25V")
      (fields (field (name "PARTNO") "DF13C-5P-1.25V(20)"))
      (libsource (lib "eagle-import") (part "DF13-5P-1.25V"))
    )
    (comp (ref "J204")
      (value "DF13C-3P-1.25V")
      (footprint "eagle-import:DF13C-3P-1.25V")
      (fields (field (name "PARTNO") "DF13C-3P-1.25V(20)"))
      (libsource (lib "eagle-import") (part "DF13-3P-1.25V"))
    )
    (comp (ref "J205")
      (value "DF13C-4P-1.25V")
      (footprint "eagle-import:DF13C-4P-1.25V")
      (fields (field (name "PARTNO") "DF13C-4P-1.25V(20)"))
      (libsource (lib "eagle-import") (part "DF13-4P-1.25V"))
    )
    (comp (ref "L201")
      (value "KNH16C104DA5TS")
      (footprint "eagle-import:KYOCERA-KNH16-DA")
      (libsource (lib "eagle-import") (part "KNH16C104DA5TS"))
    )
    (comp (ref "L202")
      (value "KNH16C104DA5TS")
      (footprint "eagle-import:KYOCERA-KNH16-DA")
      (libsource (lib "eagle-import") (part "KNH16C104DA5TS"))
    )
    (comp (ref "L203")
      (value "KNH16C104DA5TS")
      (footprint "eagle-import:KYOCERA-KNH16-DA")
      (libsource (lib "eagle-import") (part "KNH16C104DA5TS"))
    )
    (comp (ref "L204")
      (value "KNH16C104DA5TS")
      (footprint "eagle-import:KYOCERA-KNH16-DA")
      (libsource (lib "eagle-import") (part "KNH16C104DA5TS"))
    )
    (comp (ref "R201")
      (value "120R")
      (footprint "eagle-import:0402-RES")
      (fields (field (name "PARTNO") "RC0402FR-07120RL"))
      (libsource (lib "eagle-import") (part "RESISTOR0402-RES"))
    )
    (comp (ref "R202")
      (value "120R")
      (footprint "eagle-import:0402-RES")
      (fields (field (name "PARTNO") "RC0402FR-07120RL"))
      (libsource (lib "eagle-import") (part "RESISTOR0402-RES"))
    )
    (comp (ref "R203")
      (value "120R")
      (footprint "eagle-import:0402-RES")
      (fields (field (name "PARTNO") "RC0402FR-07120RL"))
      (libsource (lib "eagle-import") (part "RESISTOR0402-RES"))
    )
    (comp (ref "R204")
      (value "120R")
      (footprint "eagle-import:0402-RES")
      (fields (field (name "PARTNO") "RC0402FR-07120RL"))
      (libsource (lib "eagle-import") (part "RESISTOR0402-RES"))
    )
    (comp (ref "R205")
      (value "120R")
      (footprint "eagle-import:0402-RES")
      (fields (field (name "PARTNO") "RC0402FR-07120RL"))
      (libsource (lib "eagle-import") (part "RESISTOR0402-RES"))
    )
    (comp (ref "R206")
      (value "120R")
      (footprint "eagle-import:0402-RES")
      (fields (field (name "PARTNO") "RC0402FR-07120RL"))
      (libsource (lib "eagle-import") (part "RESISTOR0402-RES"))
    )
    (comp (ref "R207")
      (value "10K/0.1%")
      (footprint "eagle-import:0402-RES")
      (fields (field (name "PARTNO") "ERA-2AEB103X"))
      (libsource (lib "eagle-import") (part "RESISTOR0402-RES"))
    )
    (comp (ref "R208")
      (value "10K/0.1%")
      (footprint "eagle-import:0402-RES")
      (fields (field (name "PARTNO") "ERA-2AEB103X"))
      (libsource (lib "eagle-import") (part "RESISTOR0402-RES"))
    )
    (comp (ref "R209")
      (value "10K/0.1%")
      (footprint "eagle-import:0402-RES")
      (fields (field (name "PARTNO") "ERA-2AEB103X"))
      (libsource (lib "eagle-import") (part "RESISTOR0402-RES"))
    )
    (comp (ref "R210")
      (value "10K/0.1%")
      (footprint "eagle-import:0402-RES")
      (fields (field (name "PARTNO") "ERA-2AEB103X"))
      (libsource (lib "eagle-import") (part "RESISTOR0402-RES"))
    )
    (comp (ref "R211")
      (value "120R")
      (footprint "eagle-import:0402-RES")
      (fields (field (name "PARTNO") "RC0402FR-07120RL"))
      (libsource (lib "eagle-import") (part "RESISTOR0402-RES"))
    )
    (comp (ref "R212")
      (value "120R")
      (footprint "eagle-import:0402-RES")
      (fields (field (name "PARTNO") "RC0402FR-07120RL"))
      (libsource (lib "eagle-import") (part "RESISTOR0402-RES"))
    )
    (comp (ref "U201")
      (value "TXS0108QFN20")
      (footprint "eagle-import:QFN20-RGY")
      (fields (field (name "PARTNO") "TXS0108ERGYR"))
      (libsource (lib "eagle-import") (part "TXS0108QFN20"))
    )
  )
  (nets
    (net (code "1") (name "ACCEL_DRDY") (class "Default")
      (node (ref "U101") (pin "P$11") (pinfunction "GPIO17_P$11") (pintype "bidirectional"))
      (node (ref "U302") (pin "11") (pinfunction "INT1_11") (pintype "bidirectional"))
    )
    (net (code "2") (name "ALARM") (class "Default")
      (node (ref "R401") (pin "P$2") (pinfunction "2_P$2") (pintype "passive"))
      (node (ref "U101") (pin "P$12") (pinfunction "GPIO18_P$12") (pintype "bidirectional"))
    )
    (net (code "3") (name "BATT_CURRENT_SENS") (class "Default")
      (node (ref "R702") (pin "P$1") (pinfunction "1_P$1") (pintype "passive"))
      (node (ref "U501") (pin "9") (pinfunction "PC1_9") (pintype "bidirectional"))
    )
    (net (code "4") (name "BATT_VOLTAGE_SENS") (class "Default")
      (node (ref "R701") (pin "P$1") (pinfunction "1_P$1") (pintype "passive"))
      (node (ref "U501") (pin "8") (pinfunction "PC0_8") (pintype "bidirectional"))
    )
    (net (code "5") (name "GND") (class "Default")
      (node (ref "C101") (pin "P$2") (pinfunction "2_P$2") (pintype "passive"))
      (node (ref "C201") (pin "P$2") (pinfunction "2_P$2") (pintype "passive"))
      (node (ref "C202") (pin "P$2") (pinfunction "2_P$2") (pintype "passive"))
      (node (ref "C301") (pin "P$2") (pinfunction "2_P$2") (pintype "passive"))
      (node (ref "C302") (pin "P$2") (pinfunction "2_P$2") (pintype "passive"))
      (node (ref "C304") (pin "P$2") (pinfunction "2_P$2") (pintype "passive"))
      (node (ref "C306") (pin "P$2") (pinfunction "2_P$2") (pintype "passive"))
      (node (ref "C307") (pin "P$2") (pinfunction "2_P$2") (pintype "passive"))
      (node (ref "C308") (pin "P$2") (pinfunction "2_P$2") (pintype "passive"))
      (node (ref "C309") (pin "P$2") (pinfunction "2_P$2") (pintype "passive"))
      (node (ref "C312") (pin "P$2") (pinfunction "2_P$2") (pintype "passive"))
      (node (ref "C313") (pin "P$2") (pinfunction "2_P$2") (pintype "passive"))
      (node (ref "C314") (pin "P$2") (pinfunction "2_P$2") (pintype "passive"))
      (node (ref "C315") (pin "P$2") (pinfunction "2_P$2") (pintype "passive"))
      (node (ref "C401") (pin "P$2") (pinfunction "2_P$2") (pintype "passive"))
      (node (ref "C402") (pin "P$2") (pinfunction "2_P$2") (pintype "passive"))
      (node (ref "C403") (pin "P$2") (pinfunction "2_P$2") (pintype "passive"))
      (node (ref "C404") (pin "P$2") (pinfunction "2_P$2") (pintype "passive"))
      (node (ref "C501") (pin "P$1") (pinfunction "1_P$1") (pintype "passive"))
      (node (ref "C502") (pin "P$2") (pinfunction "2_P$2") (pintype "passive"))
      (node (ref "C503") (pin "P$2") (pinfunction "2_P$2") (pintype "passive"))
      (node (ref "C504") (pin "P$2") (pinfunction "2_P$2") (pintype "passive"))
      (node (ref "C505") (pin "P$2") (pinfunction "2_P$2") (pintype "passive"))
      (node (ref "C506") (pin "P$1") (pinfunction "1_P$1") (pintype "passive"))
      (node (ref "C507") (pin "P$2") (pinfunction "2_P$2") (pintype "passive"))
      (node (ref "C601") (pin "P$2") (pinfunction "2_P$2") (pintype "passive"))
      (node (ref "C701") (pin "P$2") (pinfunction "2_P$2") (pintype "passive"))
      (node (ref "C702") (pin "P$2") (pinfunction "2_P$2") (pintype "passive"))
      (node (ref "C703") (pin "P$2") (pinfunction "2_P$2") (pintype "passive"))
      (node (ref "C704") (pin "P$2") (pinfunction "2_P$2") (pintype "passive"))
      (node (ref "C705") (pin "P$2") (pinfunction "2_P$2") (pintype "passive"))
      (node (ref "C706") (pin "P$2") (pinfunction "2_P$2") (pintype "passive"))
      (node (ref "C707") (pin "P$2") (pinfunction "2_P$2") (pintype "passive"))
      (node (ref "C709") (pin "P$2") (pinfunction "2_P$2") (pintype "passive"))
      (node (ref "D201") (pin "A") (pinfunction "A_A") (pintype "passive"))
      (node (ref "D202") (pin "A") (pinfunction "A_A") (pintype "passive"))
      (node (ref "D203") (pin "A") (pinfunction "A_A") (pintype "passive"))
      (node (ref "D204") (pin "A") (pinfunction "A_A") (pintype "passive"))
      (node (ref "D401") (pin "A") (pinfunction "A_A") (pintype "passive"))
      (node (ref "D501") (pin "A") (pinfunction "A_A") (pintype "passive"))
      (node (ref "D601") (pin "A") (pinfunction "A_A") (pintype "passive"))
      (node (ref "D602") (pin "A") (pinfunction "A_A") (pintype "passive"))
      (node (ref "D703") (pin "A") (pinfunction "A_A") (pintype "passive"))
      (node (ref "GND") (pin "P$1") (pinfunction "P$1_P$1") (pintype "passive"))
      (node (ref "GND.") (pin "P$1") (pinfunction "P$1_P$1") (pintype "passive"))
      (node (ref "J201") (pin "6") (pinfunction "6_6") (pintype "passive"))
      (node (ref "J202") (pin "6") (pinfunction "6_6") (pintype "passive"))
      (node (ref "J203") (pin "3") (pinfunction "3_3") (pintype "passive"))
      (node (ref "J203") (pin "5") (pinfunction "5_5") (pintype "passive"))
      (node (ref "J204") (pin "3") (pinfunction "3_3") (pintype "passive"))
      (node (ref "J205") (pin "4") (pinfunction "4_4") (pintype "passive"))
      (node (ref "J401") (pin "2") (pinfunction "2_2") (pintype "passive"))
      (node (ref "J501") (pin "P$2") (pinfunction "P$2_P$2") (pintype "bidirectional"))
      (node (ref "J601") (pin "12") (pinfunction "S_12") (pintype "passive"))
      (node (ref "J601") (pin "15") (pinfunction "S_15") (pintype "passive"))
      (node (ref "J601") (pin "18") (pinfunction "S_18") (pintype "passive"))
      (node (ref "J601") (pin "21") (pinfunction "S_21") (pintype "passive"))
      (node (ref "J601") (pin "24") (pinfunction "S_24") (pintype "passive"))
      (node (ref "J601") (pin "27") (pinfunction "S_27") (pintype "passive"))
      (node (ref "J601") (pin "3") (pinfunction "S_3") (pintype "passive"))
      (node (ref "J601") (pin "30") (pinfunction "S_30") (pintype "passive"))
      (node (ref "J601") (pin "6") (pinfunction "S_6") (pintype "passive"))
      (node (ref "J601") (pin "9") (pinfunction "S_9") (pintype "passive"))
      (node (ref "J701") (pin "5") (pinfunction "5_5") (pintype "passive"))
      (node (ref "J701") (pin "6") (pinfunction "6_6") (pintype "passive"))
      (node (ref "JX501") (pin "3") (pinfunction "GND_3") (pintype "bidirectional"))
      (node (ref "JX502") (pin "3") (pinfunction "S_3") (pintype "passive"))
      (node (ref "JX502") (pin "5") (pinfunction "S_5") (pintype "passive"))
      (node (ref "JX502") (pin "9") (pinfunction "S_9") (pintype "passive"))
      (node (ref "L201") (pin "P$3") (pinfunction "P$3_P$3") (pintype "bidirectional"))
      (node (ref "L201") (pin "P$4") (pinfunction "P$3_P$4") (pintype "bidirectional"))
      (node (ref "L201") (pin "P$5") (pinfunction "P$3_P$5") (pintype "bidirectional"))
      (node (ref "L202") (pin "P$3") (pinfunction "P$3_P$3") (pintype "bidirectional"))
      (node (ref "L202") (pin "P$4") (pinfunction "P$3_P$4") (pintype "bidirectional"))
      (node (ref "L202") (pin "P$5") (pinfunction "P$3_P$5") (pintype "bidirectional"))
      (node (ref "L203") (pin "P$3") (pinfunction "P$3_P$3") (pintype "bidirectional"))
      (node (ref "L203") (pin "P$4") (pinfunction "P$3_P$4") (pintype "bidirectional"))
      (node (ref "L203") (pin "P$5") (pinfunction "P$3_P$5") (pintype "bidirectional"))
      (node (ref "L204") (pin "P$3") (pinfunction "P$3_P$3") (pintype "bidirectional"))
      (node (ref "L204") (pin "P$4") (pinfunction "P$3_P$4") (pintype "bidirectional"))
      (node (ref "L204") (pin "P$5") (pinfunction "P$3_P$5") (pintype "bidirectional"))
      (node (ref "L701") (pin "P$3") (pinfunction "P$3_P$3") (pintype "bidirectional"))
      (node (ref "L701") (pin "P$4") (pinfunction "P$3_P$4") (pintype "bidirectional"))
      (node (ref "L701") (pin "P$5") (pinfunction "P$3_P$5") (pintype "bidirectional"))
      (node (ref "L702") (pin "P$3") (pinfunction "P$3_P$3") (pintype "bidirectional"))
      (node (ref "L702") (pin "P$4") (pinfunction "P$3_P$4") (pintype "bidirectional"))
      (node (ref "L702") (pin "P$5") (pinfunction "P$3_P$5") (pintype "bidirectional"))
      (node (ref "R210") (pin "P$1") (pinfunction "1_P$1") (pintype "passive"))
      (node (ref "R402") (pin "P$2") (pinfunction "2_P$2") (pintype "passive"))
      (node (ref "R404") (pin "P$1") (pinfunction "1_P$1") (pintype "passive"))
      (node (ref "R406") (pin "P$2") (pinfunction "2_P$2") (pintype "passive"))
      (node (ref "R407") (pin "P$1") (pinfunction "1_P$1") (pintype "passive"))
      (node (ref "R412") (pin "P$2") (pinfunction "2_P$2") (pintype "passive"))
      (node (ref "R501") (pin "P$2") (pinfunction "2_P$2") (pintype "passive"))
      (node (ref "R502") (pin "P$2") (pinfunction "2_P$2") (pintype "passive"))
      (node (ref "R606") (pin "P$1") (pinfunction "1_P$1") (pintype "passive"))
      (node (ref "R703") (pin "P$2") (pinfunction "2_P$2") (pintype "passive"))
      (node (ref "R704") (pin "P$2") (pinfunction "2_P$2") (pintype "passive"))
      (node (ref "R706") (pin "P$2") (pinfunction "2_P$2") (pintype "passive"))
      (node (ref "R707") (pin "P$1") (pinfunction "1_P$1") (pintype "passive"))
      (node (ref "S501") (pin "B3") (pinfunction "2_B3") (pintype "passive"))
      (node (ref "U101") (pin "P$14") (pinfunction "GND_P$14") (pintype "bidirectional"))
      (node (ref "U101") (pin "P$20") (pinfunction "GND_P$20") (pintype "bidirectional"))
      (node (ref "U101") (pin "P$25") (pinfunction "GND_P$25") (pintype "bidirectional"))
      (node (ref "U101") (pin "P$30") (pinfunction "GND_P$30") (pintype "bidirectional"))
      (node (ref "U101") (pin "P$34") (pinfunction "GND_P$34") (pintype "bidirectional"))
      (node (ref "U101") (pin "P$39") (pinfunction "GND_P$39") (pintype "bidirectional"))
      (node (ref "U101") (pin "P$6") (pinfunction "GND_P$6") (pintype "bidirectional"))
      (node (ref "U101") (pin "P$9") (pinfunction "GND_P$9") (pintype "bidirectional"))
      (node (ref "U102") (pin "4") (pinfunction "VSS_4") (pintype "bidirectional"))
      (node (ref "U201") (pin "11") (pinfunction "GND_11") (pintype "power_in"))
      (node (ref "U301") (pin "10") (pinfunction "RES_P10_GND_10") (pintype "bidirectional"))
      (node (ref "U301") (pin "11") (pinfunction "RES_P11_GND_11") (pintype "bidirectional"))
      (node (ref "U301") (pin "12") (pinfunction "RES_P12_GND_12") (pintype "bidirectional"))
      (node (ref "U301") (pin "13") (pinfunction "GND_13") (pintype "bidirectional"))
      (node (ref "U301") (pin "8") (pinfunction "RES_P8_GND_8") (pintype "bidirectional"))
      (node (ref "U301") (pin "9") (pinfunction "RES_P9_GND_9") (pintype "bidirectional"))
      (node (ref "U302") (pin "10") (pinfunction "RSRV_10") (pintype "bidirectional"))
      (node (ref "U302") (pin "12") (pinfunction "GND_12") (pintype "bidirectional"))
      (node (ref "U302") (pin "13") (pinfunction "GND_13") (pintype "bidirectional"))
      (node (ref "U302") (pin "16") (pinfunction "GND_16") (pintype "bidirectional"))
      (node (ref "U302") (pin "5") (pinfunction "GND_5") (pintype "bidirectional"))
      (node (ref "U303") (pin "11") (pinfunction "FSYNC_11") (pintype "bidirectional"))
      (node (ref "U303") (pin "18") (pinfunction "GND_18") (pintype "bidirectional"))
      (node (ref "U303") (pin "20") (pinfunction "RESV_20") (pintype "bidirectional"))
      (node (ref "U304") (pin "2") (pinfunction "PS_2") (pintype "bidirectional"))
      (node (ref "U304") (pin "3") (pinfunction "GND_3") (pintype "bidirectional"))
      (node (ref "U401") (pin "5") (pinfunction "GND_5") (pintype "power_in"))
      (node (ref "U402") (pin "4") (pinfunction "GND_4") (pintype "power_in"))
      (node (ref "U501") (pin "12") (pinfunction "VSSA_12") (pintype "power_in"))
      (node (ref "U501") (pin "18") (pinfunction "VSS_18") (pintype "power_in"))
      (node (ref "U501") (pin "31") (pinfunction "VSS_31") (pintype "power_in"))
      (node (ref "U501") (pin "47") (pinfunction "VSS_47") (pintype "power_in"))
      (node (ref "U501") (pin "63") (pinfunction "VSS_63") (pintype "power_in"))
      (node (ref "U601") (pin "1") (pinfunction "~{1OE}_1") (pintype "input"))
      (node (ref "U601") (pin "4") (pinfunction "GND_4") (pintype "power_in"))
      (node (ref "U701") (pin "2") (pinfunction "GND_2") (pintype "bidirectional"))
      (node (ref "U701") (pin "GND") (pinfunction "GND_GND") (pintype "bidirectional"))
      (node (ref "U702") (pin "2") (pinfunction "GND_2") (pintype "bidirectional"))
      (node (ref "U702") (pin "4") (pinfunction "EN2_4") (pintype "bidirectional"))
      (node (ref "U702") (pin "GND") (pinfunction "GND_GND") (pintype "bidirectional"))
      (node (ref "X501") (pin "2") (pinfunction "NC_2_2") (pintype "power_in"))
      (node (ref "X501") (pin "4") (pinfunction "NC_4_4") (pintype "power_in"))
    )
    (net (code "6") (name "GYRO_DRDY") (class "Default")
      (node (ref "U101") (pin "P$31") (pinfunction "GPIO6_P$31") (pintype "bidirectional"))
      (node (ref "U301") (pin "6") (pinfunction "DRDY/INT2_6") (pintype "output"))
    )
    (net (code "7") (name "IO-BOOT0") (class "Default")
      (node (ref "IO-BOOT1101") (pin "P$1") (pinfunction "P$1_P$1") (pintype "passive"))
      (node (ref "R501") (pin "P$1") (pinfunction "1_P$1") (pintype "passive"))
      (node (ref "U501") (pin "60") (pinfunction "BOOT0_60") (pintype "input"))
    )
    (net (code "8") (name "IO-CAN_RX") (class "Default")
      (node (ref "CAN_L") (pin "P$1") (pinfunction "P$1_P$1") (pintype "passive"))
      (node (ref "R206") (pin "P$1") (pinfunction "1_P$1") (pintype "passive"))
      (node (ref "U501") (pin "61") (pinfunction "PB8_61") (pintype "bidirectional"))
    )
    (net (code "9") (name "IO-CAN_TX") (class "Default")
      (node (ref "CAN_H") (pin "P$1") (pinfunction "P$1_P$1") (pintype "passive"))
      (node (ref "R205") (pin "P$1") (pinfunction "1_P$1") (pintype "passive"))
      (node (ref "U501") (pin "62") (pinfunction "PB9_62") (pintype "bidirectional"))
    )
    (net (code "10") (name "IO-CH1") (class "Default")
      (node (ref "J601") (pin "28") (pinfunction "S_28") (pintype "passive"))
      (node (ref "U501") (pin "14") (pinfunction "PA0_14") (pintype "bidirectional"))
    )
    (net (code "11") (name "IO-CH2") (class "Default")
      (node (ref "J601") (pin "25") (pinfunction "S_25") (pintype "passive"))
      (node (ref "U501") (pin "15") (pinfunction "PA1_15") (pintype "bidirectional"))
    )
    (net (code "12") (name "IO-CH3") (class "Default")
      (node (ref "J601") (pin "22") (pinfunction "S_22") (pintype "passive"))
      (node (ref "U501") (pin "58") (pinfunction "PB6_58") (pintype "bidirectional"))
    )
    (net (code "13") (name "IO-CH4") (class "Default")
      (node (ref "J601") (pin "19") (pinfunction "S_19") (pintype "passive"))
      (node (ref "U501") (pin "59") (pinfunction "PB7_59") (pintype "bidirectional"))
    )
    (net (code "14") (name "IO-CH5") (class "Default")
      (node (ref "J601") (pin "16") (pinfunction "S_16") (pintype "passive"))
      (node (ref "U501") (pin "22") (pinfunction "PA6_22") (pintype "bidirectional"))
    )
    (net (code "15") (name "IO-CH6") (class "Default")
      (node (ref "J601") (pin "13") (pinfunction "S_13") (pintype "passive"))
      (node (ref "U501") (pin "23") (pinfunction "PA7_23") (pintype "bidirectional"))
    )
    (net (code "16") (name "IO-CH7") (class "Default")
      (node (ref "J601") (pin "10") (pinfunction "S_10") (pintype "passive"))
      (node (ref "U501") (pin "26") (pinfunction "PB0_26") (pintype "bidirectional"))
    )
    (net (code "17") (name "IO-CH8") (class "Default")
      (node (ref "J601") (pin "7") (pinfunction "S_7") (pintype "passive"))
      (node (ref "U501") (pin "27") (pinfunction "PB1_27") (pintype "bidirectional"))
    )
    (net (code "18") (name "IO-RPI-SPI_MISO") (class "Default")
      (node (ref "R503") (pin "P$1") (pinfunction "1_P$1") (pintype "passive"))
      (node (ref "U101") (pin "P$21") (pinfunction "GPIO9_P$21") (pintype "bidirectional"))
      (node (ref "U102") (pin "2") (pinfunction "Q_2") (pintype "bidirectional"))
      (node (ref "U301") (pin "4") (pinfunction "SDO/SA0_4") (pintype "bidirectional"))
      (node (ref "U302") (pin "7") (pinfunction "SDO/SA0_7") (pintype "bidirectional"))
      (node (ref "U303") (pin "9") (pinfunction "AD0/SDO_9") (pintype "bidirectional"))
      (node (ref "U304") (pin "6") (pinfunction "SDO_6") (pintype "bidirectional"))
      (node (ref "U501") (pin "56") (pinfunction "PB4_56") (pintype "bidirectional"))
    )
    (net (code "19") (name "IO-RPI-SPI_MOSI") (class "Default")
      (node (ref "U101") (pin "P$19") (pinfunction "GPIO10_P$19") (pintype "bidirectional"))
      (node (ref "U102") (pin "5") (pinfunction "D_5") (pintype "bidirectional"))
      (node (ref "U301") (pin "3") (pinfunction "SDA/SDI/SDO_3") (pintype "bidirectional"))
      (node (ref "U302") (pin "6") (pinfunction "SDA/SDI/SDO_6") (pintype "bidirectional"))
      (node (ref "U303") (pin "24") (pinfunction "SDA/SDI_24") (pintype "bidirectional"))
      (node (ref "U304") (pin "7") (pinfunction "SDI/SDA_7") (pintype "bidirectional"))
      (node (ref "U501") (pin "57") (pinfunction "PB5_57") (pintype "bidirectional"))
    )
    (net (code "20") (name "IO-RPI-SPI_NSS") (class "Default")
      (node (ref "U101") (pin "P$26") (pinfunction "GPIO7_P$26") (pintype "bidirectional"))
      (node (ref "U501") (pin "50") (pinfunction "PA15_50") (pintype "bidirectional"))
    )
    (net (code "21") (name "IO-RPI-SPI_SCK") (class "Default")
      (node (ref "JX502") (pin "6") (pinfunction "S_6") (pintype "passive"))
      (node (ref "U101") (pin "P$23") (pinfunction "GPIO11_P$23") (pintype "bidirectional"))
      (node (ref "U102") (pin "6") (pinfunction "C_6") (pintype "bidirectional"))
      (node (ref "U301") (pin "2") (pinfunction "SCL/SPC_2") (pintype "input"))
      (node (ref "U302") (pin "4") (pinfunction "SCL/SPC_4") (pintype "bidirectional"))
      (node (ref "U303") (pin "23") (pinfunction "SCL/SCLK_23") (pintype "bidirectional"))
      (node (ref "U304") (pin "8") (pinfunction "SCLK_8") (pintype "bidirectional"))
      (node (ref "U501") (pin "55") (pinfunction "PB3_55") (pintype "bidirectional"))
    )
    (net (code "22") (name "IO-SWCLK") (class "Default")
      (node (ref "JX502") (pin "4") (pinfunction "S_4") (pintype "passive"))
      (node (ref "U501") (pin "49") (pinfunction "PA14_49") (pintype "bidirectional"))
    )
    (net (code "23") (name "IO-SWDIO") (class "Default")
      (node (ref "JX502") (pin "2") (pinfunction "S_2") (pintype "passive"))
      (node (ref "U501") (pin "46") (pinfunction "PA13_46") (pintype "bidirectional"))
    )
    (net (code "24") (name "IO-USART1_RX") (class "Default")
      (node (ref "J501") (pin "P$3") (pinfunction "P$3_P$3") (pintype "bidirectional"))
      (node (ref "JX501") (pin "2") (pinfunction "+5V_2") (pintype "bidirectional"))
      (node (ref "U501") (pin "43") (pinfunction "PA10_43") (pintype "bidirectional"))
    )
    (net (code "25") (name "IO-USART1_TX") (class "Default")
      (node (ref "JX501") (pin "1") (pinfunction "PPM_1") (pintype "bidirectional"))
      (node (ref "U501") (pin "42") (pinfunction "PA9_42") (pintype "bidirectional"))
    )
    (net (code "26") (name "IO-USART2_RX") (class "Default")
      (node (ref "U201") (pin "4") (pinfunction "A3_4") (pintype "bidirectional"))
      (node (ref "U501") (pin "17") (pinfunction "PA3_17") (pintype "bidirectional"))
    )
    (net (code "27") (name "IO-USART2_TX") (class "Default")
      (node (ref "U201") (pin "5") (pinfunction "A4_5") (pintype "bidirectional"))
      (node (ref "U501") (pin "16") (pinfunction "PA2_16") (pintype "bidirectional"))
    )
    (net (code "28") (name "IO-VDD_3V3") (class "Default")
      (node (ref "C101") (pin "P$1") (pinfunction "1_P$1") (pintype "passive"))
      (node (ref "C201") (pin "P$1") (pinfunction "1_P$1") (pintype "passive"))
      (node (ref "C401") (pin "P$1") (pinfunction "1_P$1") (pintype "passive"))
      (node (ref "C502") (pin "P$1") (pinfunction "1_P$1") (pintype "passive"))
      (node (ref "C503") (pin "P$1") (pinfunction "1_P$1") (pintype "passive"))
      (node (ref "C504") (pin "P$1") (pinfunction "1_P$1") (pintype "passive"))
      (node (ref "C507") (pin "P$1") (pinfunction "1_P$1") (pintype "passive"))
      (node (ref "C601") (pin "P$1") (pinfunction "1_P$1") (pintype "passive"))
      (node (ref "C706") (pin "P$1") (pinfunction "1_P$1") (pintype "passive"))
      (node (ref "C707") (pin "P$1") (pinfunction "1_P$1") (pintype "passive"))
      (node (ref "D401") (pin "C") (pinfunction "C_C") (pintype "passive"))
      (node (ref "J402") (pin "1") (pinfunction "1_1") (pintype "passive"))
      (node (ref "JX502") (pin "1") (pinfunction "S_1") (pintype "passive"))
      (node (ref "R503") (pin "P$2") (pinfunction "2_P$2") (pintype "passive"))
      (node (ref "U102") (pin "3") (pinfunction "~{W}_3") (pintype "bidirectional"))
      (node (ref "U102") (pin "7") (pinfunction "~{HOLD}_7") (pintype "bidirectional"))
      (node (ref "U102") (pin "8") (pinfunction "VDD_8") (pintype "bidirectional"))
      (node (ref "U201") (pin "10") (pinfunction "OE_10") (pintype "input"))
      (node (ref "U201") (pin "19") (pinfunction "VCCB_19") (pintype "input"))
      (node (ref "U201") (pin "2") (pinfunction "VCCA_2") (pintype "input"))
      (node (ref "U401") (pin "1") (pinfunction "~{SHDN}_1") (pintype "input"))
      (node (ref "U401") (pin "10") (pinfunction "VIN_10") (pintype "power_in"))
      (node (ref "U501") (pin "1") (pinfunction "VBAT_1") (pintype "power_in"))
      (node (ref "U501") (pin "13") (pinfunction "VDDA_13") (pintype "power_in"))
      (node (ref "U501") (pin "19") (pinfunction "VDD_19") (pintype "power_in"))
      (node (ref "U501") (pin "32") (pinfunction "VDD_32") (pintype "power_in"))
      (node (ref "U501") (pin "48") (pinfunction "VDD_48") (pintype "power_in"))
      (node (ref "U501") (pin "64") (pinfunction "VDD_64") (pintype "power_in"))
      (node (ref "U601") (pin "8") (pinfunction "VCC_8") (pintype "power_in"))
      (node (ref "U701") (pin "8") (pinfunction "VOUT1_8") (pintype "bidirectional"))
    )
    (net (code "29") (name "IO-~{RESET}") (class "Default")
      (node (ref "C501") (pin "P$2") (pinfunction "2_P$2") (pintype "passive"))
      (node (ref "S501") (pin "A1") (pinfunction "1_A1") (pintype "passive"))
      (node (ref "U501") (pin "7") (pinfunction "NRST_7") (pintype "input"))
      (node (ref "U701") (pin "3") (pinfunction "POR2_3") (pintype "bidirectional"))
    )
    (net (code "30") (name "IO_AUX_ADC1") (class "Default")
      (node (ref "R208") (pin "P$1") (pinfunction "1_P$1") (pintype "passive"))
      (node (ref "U501") (pin "24") (pinfunction "PC4_24") (pintype "bidirectional"))
    )
    (net (code "31") (name "IO_AUX_ADC2") (class "Default")
      (node (ref "R207") (pin "P$1") (pinfunction "1_P$1") (pintype "passive"))
      (node (ref "U501") (pin "25") (pinfunction "PC5_25") (pintype "bidirectional"))
    )
    (net (code "32") (name "LED-~{RESET}") (class "Default")
      (node (ref "U101") (pin "P$7") (pinfunction "GPIO4_P$7") (pintype "bidirectional"))
      (node (ref "U401") (pin "4") (pinfunction "~{RESET}_4") (pintype "input"))
    )
    (net (code "33") (name "MAG_DRDY") (class "Default")
      (node (ref "U101") (pin "P$13") (pinfunction "GPIO27_P$13") (pintype "bidirectional"))
      (node (ref "U302") (pin "9") (pinfunction "INT2_9") (pintype "bidirectional"))
    )
    (net (code "34") (name "MPU_DRDY") (class "Default")
      (node (ref "U101") (pin "P$18") (pinfunction "GPIO24_P$18") (pintype "bidirectional"))
      (node (ref "U303") (pin "12") (pinfunction "INT_12") (pintype "bidirectional"))
    )
    (net (code "35") (name "Net-(C304-1)") (class "Default")
      (node (ref "C304") (pin "P$1") (pinfunction "1_P$1") (pintype "passive"))
      (node (ref "U301") (pin "14") (pinfunction "PLLFILT_14") (pintype "bidirectional"))
    )
    (net (code "36") (name "Net-(C309-1)") (class "Default")
      (node (ref "C309") (pin "P$1") (pinfunction "1_P$1") (pintype "passive"))
      (node (ref "U302") (pin "15") (pinfunction "C1_15") (pintype "bidirectional"))
    )
    (net (code "37") (name "Net-(C310-1)") (class "Default")
      (node (ref "C310") (pin "P$1") (pinfunction "1_P$1") (pintype "passive"))
      (node (ref "U302") (pin "2") (pinfunction "SETC_2") (pintype "bidirectional"))
    )
    (net (code "38") (name "Net-(C310-2)") (class "Default")
      (node (ref "C310") (pin "P$2") (pinfunction "2_P$2") (pintype "passive"))
      (node (ref "U302") (pin "3") (pinfunction "SETP_3") (pintype "bidirectional"))
    )
    (net (code "39") (name "Net-(C313-1)") (class "Default")
      (node (ref "C313") (pin "P$1") (pinfunction "1_P$1") (pintype "passive"))
      (node (ref "U303") (pin "10") (pinfunction "REGOUT_10") (pintype "bidirectional"))
    )
    (net (code "40") (name "Net-(C403-1)") (class "Default")
      (node (ref "C403") (pin "P$1") (pinfunction "1_P$1") (pintype "passive"))
      (node (ref "J401") (pin "1") (pinfunction "1_1") (pintype "passive"))
      (node (ref "R403") (pin "P$1") (pinfunction "1_P$1") (pintype "passive"))
      (node (ref "U402") (pin "1") (pinfunction "OUT_1") (pintype "output"))
    )
    (net (code "41") (name "Net-(C404-1)") (class "Default")
      (node (ref "C404") (pin "P$1") (pinfunction "1_P$1") (pintype "passive"))
      (node (ref "R405") (pin "P$1") (pinfunction "1_P$1") (pintype "passive"))
      (node (ref "U402") (pin "6") (pinfunction "VCC_6") (pintype "bidirectional"))
    )
    (net (code "42") (name "Net-(C505-1)") (class "Default")
      (node (ref "C505") (pin "P$1") (pinfunction "1_P$1") (pintype "passive"))
      (node (ref "U501") (pin "5") (pinfunction "PH0/OSC<=_5") (pintype "bidirectional"))
      (node (ref "X501") (pin "3") (pinfunction "3_3") (pintype "bidirectional"))
    )
    (net (code "43") (name "Net-(C506-2)") (class "Default")
      (node (ref "C506") (pin "P$2") (pinfunction "2_P$2") (pintype "passive"))
      (node (ref "U501") (pin "6") (pinfunction "PH1/OSC=>_6") (pintype "bidirectional"))
      (node (ref "X501") (pin "1") (pinfunction "1_1") (pintype "bidirectional"))
    )
    (net (code "44") (name "Net-(C702-1)") (class "Default")
      (node (ref "C702") (pin "P$1") (pinfunction "1_P$1") (pintype "passive"))
      (node (ref "U701") (pin "6") (pinfunction "CSET_6") (pintype "bidirectional"))
    )
    (net (code "45") (name "Net-(D201-PadC)") (class "Default")
      (node (ref "D201") (pin "C") (pinfunction "C_C") (pintype "passive"))
      (node (ref "J201") (pin "1") (pinfunction "1_1") (pintype "passive"))
      (node (ref "L201") (pin "P$2") (pinfunction "P$2_P$2") (pintype "bidirectional"))
    )
    (net (code "46") (name "Net-(D202-PadC)") (class "Default")
      (node (ref "D202") (pin "C") (pinfunction "C_C") (pintype "passive"))
      (node (ref "J202") (pin "1") (pinfunction "1_1") (pintype "passive"))
      (node (ref "L202") (pin "P$2") (pinfunction "P$2_P$2") (pintype "bidirectional"))
    )
    (net (code "47") (name "Net-(D203-PadC)") (class "Default")
      (node (ref "D203") (pin "C") (pinfunction "C_C") (pintype "passive"))
      (node (ref "J203") (pin "1") (pinfunction "1_1") (pintype "passive"))
      (node (ref "L203") (pin "P$2") (pinfunction "P$2_P$2") (pintype "bidirectional"))
    )
    (net (code "48") (name "Net-(D204-PadC)") (class "Default")
      (node (ref "D204") (pin "C") (pinfunction "C_C") (pintype "passive"))
      (node (ref "J204") (pin "1") (pinfunction "1_1") (pintype "passive"))
      (node (ref "J205") (pin "1") (pinfunction "1_1") (pintype "passive"))
      (node (ref "L204") (pin "P$2") (pinfunction "P$2_P$2") (pintype "bidirectional"))
    )
    (net (code "49") (name "Net-(J601A-S)") (class "Default")
      (node (ref "J601") (pin "1") (pinfunction "S_1") (pintype "passive"))
      (node (ref "R602") (pin "P$2") (pinfunction "2_P$2") (pintype "passive"))
    )
    (net (code "50") (name "Net-(J601J-S)") (class "Default")
      (node (ref "J601") (pin "4") (pinfunction "S_4") (pintype "passive"))
      (node (ref "R603") (pin "P$2") (pinfunction "2_P$2") (pintype "passive"))
    )
    (net (code "51") (name "Net-(L401-2)") (class "Default")
      (node (ref "L401") (pin "P$2") (pinfunction "2_P$2") (pintype "passive"))
      (node (ref "U402") (pin "5") (pinfunction "SW_5") (pintype "passive"))
    )
    (net (code "52") (name "Net-(R201-1)") (class "Default")
      (node (ref "R201") (pin "P$1") (pinfunction "1_P$1") (pintype "passive"))
      (node (ref "U201") (pin "20") (pinfunction "B1_20") (pintype "bidirectional"))
    )
    (net (code "53") (name "Net-(R202-1)") (class "Default")
      (node (ref "R202") (pin "P$1") (pinfunction "1_P$1") (pintype "passive"))
      (node (ref "U201") (pin "18") (pinfunction "B2_18") (pintype "bidirectional"))
    )
    (net (code "54") (name "Net-(R203-1)") (class "Default")
      (node (ref "R203") (pin "P$1") (pinfunction "1_P$1") (pintype "passive"))
      (node (ref "U201") (pin "17") (pinfunction "B3_17") (pintype "bidirectional"))
    )
    (net (code "55") (name "Net-(R204-1)") (class "Default")
      (node (ref "R204") (pin "P$1") (pinfunction "1_P$1") (pintype "passive"))
      (node (ref "U201") (pin "16") (pinfunction "B4_16") (pintype "bidirectional"))
    )
    (net (code "56") (name "Net-(R205-2)") (class "Default")
      (node (ref "J202") (pin "4") (pinfunction "4_4") (pintype "passive"))
      (node (ref "R205") (pin "P$2") (pinfunction "2_P$2") (pintype "passive"))
    )
    (net (code "57") (name "Net-(R206-2)") (class "Default")
      (node (ref "J202") (pin "5") (pinfunction "5_5") (pintype "passive"))
      (node (ref "R206") (pin "P$2") (pinfunction "2_P$2") (pintype "passive"))
    )
    (net (code "58") (name "Net-(R207-2)") (class "Default")
      (node (ref "J203") (pin "2") (pinfunction "2_2") (pintype "passive"))
      (node (ref "R207") (pin "P$2") (pinfunction "2_P$2") (pintype "passive"))
    )
    (net (code "59") (name "Net-(R208-2)") (class "Default")
      (node (ref "J203") (pin "4") (pinfunction "4_4") (pintype "passive"))
      (node (ref "R208") (pin "P$2") (pinfunction "2_P$2") (pintype "passive"))
    )
    (net (code "60") (name "Net-(R211-2)") (class "Default")
      (node (ref "J205") (pin "2") (pinfunction "2_2") (pintype "passive"))
      (node (ref "R211") (pin "P$2") (pinfunction "2_P$2") (pintype "passive"))
    )
    (net (code "61") (name "Net-(R212-2)") (class "Default")
      (node (ref "J205") (pin "3") (pinfunction "3_3") (pintype "passive"))
      (node (ref "R212") (pin "P$2") (pinfunction "2_P$2") (pintype "passive"))
    )
    (net (code "62") (name "Net-(R401-1)") (class "Default")
      (node (ref "R401") (pin "P$1") (pinfunction "1_P$1") (pintype "passive"))
      (node (ref "U402") (pin "7") (pinfunction "+IN_7") (pintype "input"))
    )
    (net (code "63") (name "Net-(R402-1)") (class "Default")
      (node (ref "R402") (pin "P$1") (pinfunction "1_P$1") (pintype "passive"))
      (node (ref "R403") (pin "P$2") (pinfunction "2_P$2") (pintype "passive"))
      (node (ref "U402") (pin "8") (pinfunction "-IN_8") (pintype "input"))
    )
    (net (code "64") (name "Net-(R404-2)") (class "Default")
      (node (ref "R404") (pin "P$2") (pinfunction "2_P$2") (pintype "passive"))
      (node (ref "U401") (pin "6") (pinfunction "REXT_6") (pintype "bidirectional"))
    )
    (net (code "65") (name "Net-(R405-2)") (class "Default")
      (node (ref "R405") (pin "P$2") (pinfunction "2_P$2") (pintype "passive"))
      (node (ref "R406") (pin "P$1") (pinfunction "1_P$1") (pintype "passive"))
      (node (ref "U402") (pin "2") (pinfunction "FB_2") (pintype "bidirectional"))
    )
    (net (code "66") (name "Net-(R407-2)") (class "Default")
      (node (ref "LED401") (pin "C") (pinfunction "C_C") (pintype "passive"))
      (node (ref "R407") (pin "P$2") (pinfunction "2_P$2") (pintype "passive"))
    )
    (net (code "67") (name "Net-(R408-1)") (class "Default")
      (node (ref "R408") (pin "P$1") (pinfunction "1_P$1") (pintype "passive"))
      (node (ref "R409") (pin "P$2") (pinfunction "2_P$2") (pintype "passive"))
    )
    (net (code "68") (name "Net-(R408-2)") (class "Default")
      (node (ref "LED402") (pin "C") (pinfunction "C_C") (pintype "passive"))
      (node (ref "R408") (pin "P$2") (pinfunction "2_P$2") (pintype "passive"))
    )
    (net (code "69") (name "Net-(R410-2)") (class "Default")
      (node (ref "LED403") (pin "C") (pinfunction "C_C") (pintype "passive"))
      (node (ref "R410") (pin "P$2") (pinfunction "2_P$2") (pintype "passive"))
    )
    (net (code "70") (name "Net-(R411-1)") (class "Default")
      (node (ref "J402") (pin "2") (pinfunction "2_2") (pintype "passive"))
      (node (ref "R411") (pin "P$1") (pinfunction "1_P$1") (pintype "passive"))
    )
    (net (code "71") (name "Net-(R502-1)") (class "Default")
      (node (ref "R502") (pin "P$1") (pinfunction "1_P$1") (pintype "passive"))
      (node (ref "U501") (pin "28") (pinfunction "PB2_28") (pintype "bidirectional"))
    )
    (net (code "72") (name "Net-(R601-2)") (class "Default")
      (node (ref "D602") (pin "C") (pinfunction "C_C") (pintype "passive"))
      (node (ref "R601") (pin "P$2") (pinfunction "2_P$2") (pintype "passive"))
      (node (ref "R603") (pin "P$1") (pinfunction "1_P$1") (pintype "passive"))
      (node (ref "U601") (pin "3") (pinfunction "2Y_3") (pintype "bidirectional"))
    )
    (net (code "73") (name "Net-(R604-1)") (class "Default")
      (node (ref "R604") (pin "P$1") (pinfunction "1_P$1") (pintype "passive"))
      (node (ref "R605") (pin "P$2") (pinfunction "2_P$2") (pintype "passive"))
    )
    (net (code "74") (name "Net-(R701-2)") (class "Default")
      (node (ref "L702") (pin "P$2") (pinfunction "P$2_P$2") (pintype "bidirectional"))
      (node (ref "R701") (pin "P$2") (pinfunction "2_P$2") (pintype "passive"))
    )
    (net (code "75") (name "Net-(R702-2)") (class "Default")
      (node (ref "L701") (pin "P$2") (pinfunction "P$2_P$2") (pintype "bidirectional"))
      (node (ref "R702") (pin "P$2") (pinfunction "2_P$2") (pintype "passive"))
    )
    (net (code "76") (name "Net-(R703-1)") (class "Default")
      (node (ref "J701") (pin "4") (pinfunction "4_4") (pintype "passive"))
      (node (ref "L702") (pin "P$1") (pinfunction "P$1_P$1") (pintype "bidirectional"))
      (node (ref "R703") (pin "P$1") (pinfunction "1_P$1") (pintype "passive"))
    )
    (net (code "77") (name "Net-(R704-1)") (class "Default")
      (node (ref "J701") (pin "3") (pinfunction "3_3") (pintype "passive"))
      (node (ref "L701") (pin "P$1") (pinfunction "P$1_P$1") (pintype "bidirectional"))
      (node (ref "R704") (pin "P$1") (pinfunction "1_P$1") (pintype "passive"))
    )
    (net (code "78") (name "Net-(U401-OUT0)") (class "Default")
      (node (ref "U401") (pin "9") (pinfunction "OUT0_9") (pintype "open_collector"))
      (node (ref "U403") (pin "C1") (pinfunction "C_C1") (pintype "passive"))
    )
    (net (code "79") (name "Net-(U401-OUT1)") (class "Default")
      (node (ref "U401") (pin "8") (pinfunction "OUT1_8") (pintype "open_collector"))
      (node (ref "U403") (pin "C2") (pinfunction "C_C2") (pintype "passive"))
    )
    (net (code "80") (name "Net-(U401-OUT2)") (class "Default")
      (node (ref "U401") (pin "7") (pinfunction "OUT2_7") (pintype "open_collector"))
      (node (ref "U403") (pin "C3") (pinfunction "C_C3") (pintype "passive"))
    )
    (net (code "81") (name "PPM_INPUT") (class "Default")
      (node (ref "D601") (pin "C") (pinfunction "C_C") (pintype "passive"))
      (node (ref "R602") (pin "P$1") (pinfunction "1_P$1") (pintype "passive"))
      (node (ref "U501") (pin "41") (pinfunction "PA8_41") (pintype "bidirectional"))
      (node (ref "U601") (pin "2") (pinfunction "1A_2") (pintype "bidirectional"))
    )
    (net (code "82") (name "PRESSURE_SENS") (class "Default")
      (node (ref "C202") (pin "P$1") (pinfunction "1_P$1") (pintype "passive"))
      (node (ref "R209") (pin "P$1") (pinfunction "1_P$1") (pintype "passive"))
      (node (ref "R210") (pin "P$2") (pinfunction "2_P$2") (pintype "passive"))
      (node (ref "U501") (pin "11") (pinfunction "PC3_11") (pintype "bidirectional"))
    )
    (net (code "83") (name "PRESSURE_SENS_IN") (class "Default")
      (node (ref "ADC_PR") (pin "P$1") (pinfunction "P$1_P$1") (pintype "passive"))
      (node (ref "J204") (pin "2") (pinfunction "2_2") (pintype "passive"))
      (node (ref "R209") (pin "P$2") (pinfunction "2_P$2") (pintype "passive"))
    )
    (net (code "84") (name "RPI-I2C_SCL") (class "Default")
      (node (ref "R211") (pin "P$1") (pinfunction "1_P$1") (pintype "passive"))
      (node (ref "U101") (pin "P$5") (pinfunction "GPIO3_P$5") (pintype "bidirectional"))
      (node (ref "U401") (pin "3") (pinfunction "SCL_3") (pintype "bidirectional"))
    )
    (net (code "85") (name "RPI-I2C_SDA") (class "Default")
      (node (ref "R212") (pin "P$1") (pinfunction "1_P$1") (pintype "passive"))
      (node (ref "U101") (pin "P$3") (pinfunction "GPIO2_P$3") (pintype "bidirectional"))
      (node (ref "U401") (pin "2") (pinfunction "SDA_2") (pintype "bidirectional"))
    )
    (net (code "86") (name "RPI-UART_RX") (class "Default")
      (node (ref "U101") (pin "P$10") (pinfunction "GPIO15_P$10") (pintype "bidirectional"))
      (node (ref "U201") (pin "1") (pinfunction "A1_1") (pintype "bidirectional"))
    )
    (net (code "87") (name "RPI-UART_TX") (class "Default")
      (node (ref "U101") (pin "P$8") (pinfunction "GPIO14_P$8") (pintype "bidirectional"))
      (node (ref "U201") (pin "3") (pinfunction "A2_3") (pintype "bidirectional"))
    )
    (net (code "88") (name "RSSI_IN") (class "Default")
      (node (ref "R601") (pin "P$1") (pinfunction "1_P$1") (pintype "passive"))
      (node (ref "U501") (pin "21") (pinfunction "PA5_21") (pintype "bidirectional"))
      (node (ref "U501") (pin "45") (pinfunction "PA12_45") (pintype "bidirectional"))
    )
    (net (code "89") (name "RX-VDD_5V5") (class "Default")
      (node (ref "F701") (pin "2") (pinfunction "2_2") (pintype "bidirectional"))
      (node (ref "J601") (pin "2") (pinfunction "S_2") (pintype "passive"))
    )
    (net (code "90") (name "SAFETY") (class "Default")
      (node (ref "J402") (pin "3") (pinfunction "3_3") (pintype "passive"))
      (node (ref "R412") (pin "P$1") (pinfunction "1_P$1") (pintype "passive"))
      (node (ref "U501") (pin "38") (pinfunction "PC7_38") (pintype "bidirectional"))
    )
    (net (code "91") (name "SBUS_INPUT") (class "Default")
      (node (ref "U501") (pin "30") (pinfunction "PB11_30") (pintype "bidirectional"))
      (node (ref "U601") (pin "6") (pinfunction "1Y_6") (pintype "bidirectional"))
    )
    (net (code "92") (name "SBUS_OUTPUT") (class "Default")
      (node (ref "U501") (pin "29") (pinfunction "PB10_29") (pintype "bidirectional"))
      (node (ref "U601") (pin "5") (pinfunction "2A_5") (pintype "bidirectional"))
    )
    (net (code "93") (name "SERIAL1_RX") (class "Default")
      (node (ref "J201") (pin "3") (pinfunction "3_3") (pintype "passive"))
      (node (ref "R203") (pin "P$2") (pinfunction "2_P$2") (pintype "passive"))
      (node (ref "S1RX") (pin "P$1") (pinfunction "P$1_P$1") (pintype "passive"))
    )
    (net (code "94") (name "SERIAL1_TX") (class "Default")
      (node (ref "J201") (pin "2") (pinfunction "2_2") (pintype "passive"))
      (node (ref "R204") (pin "P$2") (pinfunction "2_P$2") (pintype "passive"))
      (node (ref "S1TX") (pin "P$1") (pinfunction "P$1_P$1") (pintype "passive"))
    )
    (net (code "95") (name "SERIAL2_RX") (class "Default")
      (node (ref "J202") (pin "3") (pinfunction "3_3") (pintype "passive"))
      (node (ref "R201") (pin "P$2") (pinfunction "2_P$2") (pintype "passive"))
      (node (ref "S2RX") (pin "P$1") (pinfunction "P$1_P$1") (pintype "passive"))
    )
    (net (code "96") (name "SERIAL2_TX") (class "Default")
      (node (ref "J202") (pin "2") (pinfunction "2_2") (pintype "passive"))
      (node (ref "R202") (pin "P$2") (pinfunction "2_P$2") (pintype "passive"))
      (node (ref "S2TX") (pin "P$1") (pinfunction "P$1_P$1") (pintype "passive"))
    )
    (net (code "97") (name "VDD_3V3_SENSORS") (class "Default")
      (node (ref "C301") (pin "P$1") (pinfunction "1_P$1") (pintype "passive"))
      (node (ref "C302") (pin "P$1") (pinfunction "1_P$1") (pintype "passive"))
      (node (ref "C306") (pin "P$1") (pinfunction "1_P$1") (pintype "passive"))
      (node (ref "C307") (pin "P$1") (pinfunction "1_P$1") (pintype "passive"))
      (node (ref "C308") (pin "P$1") (pinfunction "1_P$1") (pintype "passive"))
      (node (ref "C312") (pin "P$1") (pinfunction "1_P$1") (pintype "passive"))
      (node (ref "C314") (pin "P$1") (pinfunction "1_P$1") (pintype "passive"))
      (node (ref "C315") (pin "P$1") (pinfunction "1_P$1") (pintype "passive"))
      (node (ref "C703") (pin "P$1") (pinfunction "1_P$1") (pintype "passive"))
      (node (ref "C704") (pin "P$1") (pinfunction "1_P$1") (pintype "passive"))
      (node (ref "U301") (pin "1") (pinfunction "VDD_IO_1") (pintype "bidirectional"))
      (node (ref "U301") (pin "15") (pinfunction "RES_P15_VDD_15") (pintype "bidirectional"))
      (node (ref "U301") (pin "16") (pinfunction "VDD_16") (pintype "bidirectional"))
      (node (ref "U302") (pin "1") (pinfunction "VDD_IO_1") (pintype "bidirectional"))
      (node (ref "U302") (pin "14") (pinfunction "VDD_14") (pintype "bidirectional"))
      (node (ref "U303") (pin "1") (pinfunction "NC_1") (pintype "bidirectional"))
      (node (ref "U303") (pin "13") (pinfunction "VDD_13") (pintype "bidirectional"))
      (node (ref "U303") (pin "8") (pinfunction "VDDIO_8") (pintype "bidirectional"))
      (node (ref "U304") (pin "1") (pinfunction "VDD_1") (pintype "bidirectional"))
      (node (ref "U701") (pin "7") (pinfunction "VOUT2_7") (pintype "bidirectional"))
    )
    (net (code "98") (name "VDD_3V3_SPEKTRUM") (class "Default")
      (node (ref "C709") (pin "P$1") (pinfunction "1_P$1") (pintype "passive"))
      (node (ref "D501") (pin "C") (pinfunction "C_C") (pintype "passive"))
      (node (ref "J501") (pin "P$1") (pinfunction "P$1_P$1") (pintype "bidirectional"))
      (node (ref "U702") (pin "8") (pinfunction "VOUT1_8") (pintype "bidirectional"))
    )
    (net (code "99") (name "VDD_3V3_SPEKTRUM_EN") (class "Default")
      (node (ref "R707") (pin "P$2") (pinfunction "2_P$2") (pintype "passive"))
      (node (ref "U501") (pin "39") (pinfunction "PC8_39") (pintype "bidirectional"))
      (node (ref "U702") (pin "5") (pinfunction "EN1_5") (pintype "bidirectional"))
    )
    (net (code "100") (name "VDD_5V_BRICK") (class "Default")
      (node (ref "D701") (pin "A") (pinfunction "A_A") (pintype "passive"))
      (node (ref "J701") (pin "1") (pinfunction "1_1") (pintype "passive"))
      (node (ref "J701") (pin "2") (pinfunction "2_2") (pintype "passive"))
      (node (ref "VDD_5V_BRICK") (pin "P$1") (pinfunction "P$1_P$1") (pintype "passive"))
    )
    (net (code "101") (name "VDD_5V_IN") (class "Default")
      (node (ref "C402") (pin "P$1") (pinfunction "1_P$1") (pintype "passive"))
      (node (ref "C701") (pin "P$1") (pinfunction "1_P$1") (pintype "passive"))
      (node (ref "C705") (pin "P$1") (pinfunction "1_P$1") (pintype "passive"))
      (node (ref "D701") (pin "C") (pinfunction "C_C") (pintype "passive"))
      (node (ref "D702") (pin "C") (pinfunction "C_C") (pintype "passive"))
      (node (ref "D703") (pin "C") (pinfunction "C_C") (pintype "passive"))
      (node (ref "F701") (pin "1") (pinfunction "1_1") (pintype "bidirectional"))
      (node (ref "F702") (pin "1") (pinfunction "1_1") (pintype "bidirectional"))
      (node (ref "L401") (pin "P$1") (pinfunction "1_P$1") (pintype "passive"))
      (node (ref "LED401") (pin "A") (pinfunction "A_A") (pintype "passive"))
      (node (ref "LED402") (pin "A") (pinfunction "A_A") (pintype "passive"))
      (node (ref "LED403") (pin "A") (pinfunction "A_A") (pintype "passive"))
      (node (ref "R705") (pin "P$2") (pinfunction "2_P$2") (pintype "passive"))
      (node (ref "U101") (pin "P$2") (pinfunction "5V_P$2") (pintype "bidirectional"))
      (node (ref "U101") (pin "P$4") (pinfunction "5V_P$4") (pintype "bidirectional"))
      (node (ref "U402") (pin "3") (pinfunction "VIN_3") (pintype "power_in"))
      (node (ref "U403") (pin "A1") (pinfunction "A_A1") (pintype "passive"))
      (node (ref "U403") (pin "A2") (pinfunction "A_A2") (pintype "passive"))
      (node (ref "U403") (pin "A3") (pinfunction "A_A3") (pintype "passive"))
      (node (ref "U701") (pin "1") (pinfunction "VIN_1") (pintype "bidirectional"))
      (node (ref "U701") (pin "4") (pinfunction "EN2_4") (pintype "bidirectional"))
      (node (ref "U701") (pin "5") (pinfunction "EN1_5") (pintype "bidirectional"))
      (node (ref "U702") (pin "1") (pinfunction "VIN_1") (pintype "bidirectional"))
      (node (ref "VDD_5V_IN") (pin "P$1") (pinfunction "P$1_P$1") (pintype "passive"))
    )
    (net (code "102") (name "VDD_5V_PERIPH") (class "Default")
      (node (ref "F702") (pin "2") (pinfunction "2_2") (pintype "bidirectional"))
      (node (ref "L201") (pin "P$1") (pinfunction "P$1_P$1") (pintype "bidirectional"))
      (node (ref "L202") (pin "P$1") (pinfunction "P$1_P$1") (pintype "bidirectional"))
      (node (ref "L203") (pin "P$1") (pinfunction "P$1_P$1") (pintype "bidirectional"))
      (node (ref "L204") (pin "P$1") (pinfunction "P$1_P$1") (pintype "bidirectional"))
    )
    (net (code "103") (name "VDD_5V_SENS") (class "Default")
      (node (ref "R705") (pin "P$1") (pinfunction "1_P$1") (pintype "passive"))
      (node (ref "R706") (pin "P$1") (pinfunction "1_P$1") (pintype "passive"))
      (node (ref "U501") (pin "10") (pinfunction "PC2_10") (pintype "bidirectional"))
    )
    (net (code "104") (name "VDD_SERVO") (class "Default")
      (node (ref "D702") (pin "A") (pinfunction "A_A") (pintype "passive"))
      (node (ref "J601") (pin "11") (pinfunction "S_11") (pintype "passive"))
      (node (ref "J601") (pin "14") (pinfunction "S_14") (pintype "passive"))
      (node (ref "J601") (pin "17") (pinfunction "S_17") (pintype "passive"))
      (node (ref "J601") (pin "20") (pinfunction "S_20") (pintype "passive"))
      (node (ref "J601") (pin "23") (pinfunction "S_23") (pintype "passive"))
      (node (ref "J601") (pin "26") (pinfunction "S_26") (pintype "passive"))
      (node (ref "J601") (pin "29") (pinfunction "S_29") (pintype "passive"))
      (node (ref "J601") (pin "5") (pinfunction "S_5") (pintype "passive"))
      (node (ref "J601") (pin "8") (pinfunction "S_8") (pintype "passive"))
      (node (ref "R604") (pin "P$2") (pinfunction "2_P$2") (pintype "passive"))
      (node (ref "VDD_SERVO") (pin "P$1") (pinfunction "P$1_P$1") (pintype "passive"))
    )
    (net (code "105") (name "VDD_SERVO_SENS") (class "Default")
      (node (ref "R605") (pin "P$1") (pinfunction "1_P$1") (pintype "passive"))
      (node (ref "R606") (pin "P$2") (pinfunction "2_P$2") (pintype "passive"))
      (node (ref "U501") (pin "20") (pinfunction "PA4_20") (pintype "bidirectional"))
    )
    (net (code "106") (name "unconnected-(J201-Pad4)") (class "Default")
      (node (ref "J201") (pin "4") (pinfunction "4_4") (pintype "passive"))
    )
    (net (code "107") (name "unconnected-(J201-Pad5)") (class "Default")
      (node (ref "J201") (pin "5") (pinfunction "5_5") (pintype "passive"))
    )
    (net (code "108") (name "unconnected-(JX502A-S-Pad10)") (class "Default")
      (node (ref "JX502") (pin "10") (pinfunction "S_10") (pintype "passive"))
    )
    (net (code "109") (name "unconnected-(JX502F-S-Pad8)") (class "Default")
      (node (ref "JX502") (pin "8") (pinfunction "S_8") (pintype "passive"))
    )
    (net (code "110") (name "unconnected-(U101-3V3-PadP$1)") (class "Default")
      (node (ref "U101") (pin "P$1") (pinfunction "3V3_P$1") (pintype "bidirectional"))
    )
    (net (code "111") (name "unconnected-(U101-3V3-PadP$17)") (class "Default")
      (node (ref "U101") (pin "P$17") (pinfunction "3V3_P$17") (pintype "bidirectional"))
    )
    (net (code "112") (name "unconnected-(U101-GPIO8-PadP$24)") (class "Default")
      (node (ref "U101") (pin "P$24") (pinfunction "GPIO8_P$24") (pintype "bidirectional"))
    )
    (net (code "113") (name "unconnected-(U101-GPIO13-PadP$33)") (class "Default")
      (node (ref "U101") (pin "P$33") (pinfunction "GPIO13_P$33") (pintype "bidirectional"))
    )
    (net (code "114") (name "unconnected-(U101-GPIO16-PadP$36)") (class "Default")
      (node (ref "U101") (pin "P$36") (pinfunction "GPIO16_P$36") (pintype "bidirectional"))
    )
    (net (code "115") (name "unconnected-(U101-GPIO19-PadP$35)") (class "Default")
      (node (ref "U101") (pin "P$35") (pinfunction "GPIO19_P$35") (pintype "bidirectional"))
    )
    (net (code "116") (name "unconnected-(U101-GPIO20-PadP$38)") (class "Default")
      (node (ref "U101") (pin "P$38") (pinfunction "GPIO20_P$38") (pintype "bidirectional"))
    )
    (net (code "117") (name "unconnected-(U101-GPIO21-PadP$40)") (class "Default")
      (node (ref "U101") (pin "P$40") (pinfunction "GPIO21_P$40") (pintype "bidirectional"))
    )
    (net (code "118") (name "unconnected-(U101-GPIO26-PadP$37)") (class "Default")
      (node (ref "U101") (pin "P$37") (pinfunction "GPIO26_P$37") (pintype "bidirectional"))
    )
    (net (code "119") (name "unconnected-(U101-ID_SC*-PadP$28)") (class "Default")
      (node (ref "U101") (pin "P$28") (pinfunction "ID_SC*_P$28") (pintype "bidirectional"))
    )
    (net (code "120") (name "unconnected-(U101-ID_SD*-PadP$27)") (class "Default")
      (node (ref "U101") (pin "P$27") (pinfunction "ID_SD*_P$27") (pintype "bidirectional"))
    )
    (net (code "121") (name "unconnected-(U201-A5-Pad6)") (class "Default")
      (node (ref "U201") (pin "6") (pinfunction "A5_6") (pintype "bidirectional"))
    )
    (net (code "122") (name "unconnected-(U201-A6-Pad7)") (class "Default")
      (node (ref "U201") (pin "7") (pinfunction "A6_7") (pintype "bidirectional"))
    )
    (net (code "123") (name "unconnected-(U201-A7-Pad8)") (class "Default")
      (node (ref "U201") (pin "8") (pinfunction "A7_8") (pintype "bidirectional"))
    )
    (net (code "124") (name "unconnected-(U201-A8-Pad9)") (class "Default")
      (node (ref "U201") (pin "9") (pinfunction "A8_9") (pintype "bidirectional"))
    )
    (net (code "125") (name "unconnected-(U201-B5-Pad15)") (class "Default")
      (node (ref "U201") (pin "15") (pinfunction "B5_15") (pintype "bidirectional"))
    )
    (net (code "126") (name "unconnected-(U201-B6-Pad14)") (class "Default")
      (node (ref "U201") (pin "14") (pinfunction "B6_14") (pintype "bidirectional"))
    )
    (net (code "127") (name "unconnected-(U201-B7-Pad13)") (class "Default")
      (node (ref "U201") (pin "13") (pinfunction "B7_13") (pintype "bidirectional"))
    )
    (net (code "128") (name "unconnected-(U201-B8-Pad12)") (class "Default")
      (node (ref "U201") (pin "12") (pinfunction "B8_12") (pintype "bidirectional"))
    )
    (net (code "129") (name "unconnected-(U301-INT1-Pad7)") (class "Default")
      (node (ref "U301") (pin "7") (pinfunction "INT1_7") (pintype "output"))
    )
    (net (code "130") (name "unconnected-(U303-AUX_CL-Pad7)") (class "Default")
      (node (ref "U303") (pin "7") (pinfunction "AUX_CL_7") (pintype "bidirectional"))
    )
    (net (code "131") (name "unconnected-(U303-AUX_DA-Pad21)") (class "Default")
      (node (ref "U303") (pin "21") (pinfunction "AUX_DA_21") (pintype "bidirectional"))
    )
    (net (code "132") (name "unconnected-(U303-NC-Pad2)") (class "Default")
      (node (ref "U303") (pin "2") (pinfunction "NC_2") (pintype "bidirectional"))
    )
    (net (code "133") (name "unconnected-(U303-NC-Pad3)") (class "Default")
      (node (ref "U303") (pin "3") (pinfunction "NC_3") (pintype "bidirectional"))
    )
    (net (code "134") (name "unconnected-(U303-NC-Pad4)") (class "Default")
      (node (ref "U303") (pin "4") (pinfunction "NC_4") (pintype "bidirectional"))
    )
    (net (code "135") (name "unconnected-(U303-NC-Pad5)") (class "Default")
      (node (ref "U303") (pin "5") (pinfunction "NC_5") (pintype "bidirectional"))
    )
    (net (code "136") (name "unconnected-(U303-NC-Pad6)") (class "Default")
      (node (ref "U303") (pin "6") (pinfunction "NC_6") (pintype "bidirectional"))
    )
    (net (code "137") (name "unconnected-(U303-NC-Pad14)") (class "Default")
      (node (ref "U303") (pin "14") (pinfunction "NC_14") (pintype "bidirectional"))
    )
    (net (code "138") (name "unconnected-(U303-NC-Pad15)") (class "Default")
      (node (ref "U303") (pin "15") (pinfunction "NC_15") (pintype "bidirectional"))
    )
    (net (code "139") (name "unconnected-(U303-NC-Pad16)") (class "Default")
      (node (ref "U303") (pin "16") (pinfunction "NC_16") (pintype "bidirectional"))
    )
    (net (code "140") (name "unconnected-(U303-NC-Pad17)") (class "Default")
      (node (ref "U303") (pin "17") (pinfunction "NC_17") (pintype "bidirectional"))
    )
    (net (code "141") (name "unconnected-(U303-RESV-Pad19)") (class "Default")
      (node (ref "U303") (pin "19") (pinfunction "RESV_19") (pintype "bidirectional"))
    )
    (net (code "142") (name "unconnected-(U304-CSB1-Pad4)") (class "Default")
      (node (ref "U304") (pin "4") (pinfunction "CSB1_4") (pintype "bidirectional"))
    )
    (net (code "143") (name "unconnected-(U501B-PC9-Pad40)") (class "Default")
      (node (ref "U501") (pin "40") (pinfunction "PC9_40") (pintype "bidirectional"))
    )
    (net (code "144") (name "unconnected-(U501B-PC10-Pad51)") (class "Default")
      (node (ref "U501") (pin "51") (pinfunction "PC10_51") (pintype "bidirectional"))
    )
    (net (code "145") (name "unconnected-(U501B-PC11-Pad52)") (class "Default")
      (node (ref "U501") (pin "52") (pinfunction "PC11_52") (pintype "bidirectional"))
    )
    (net (code "146") (name "unconnected-(U501B-PC12-Pad53)") (class "Default")
      (node (ref "U501") (pin "53") (pinfunction "PC12_53") (pintype "bidirectional"))
    )
    (net (code "147") (name "unconnected-(U501B-PC13-Pad2)") (class "Default")
      (node (ref "U501") (pin "2") (pinfunction "PC13_2") (pintype "bidirectional"))
    )
    (net (code "148") (name "unconnected-(U501B-PC14-Pad3)") (class "Default")
      (node (ref "U501") (pin "3") (pinfunction "PC14_3") (pintype "bidirectional"))
    )
    (net (code "149") (name "unconnected-(U501B-PC15-Pad4)") (class "Default")
      (node (ref "U501") (pin "4") (pinfunction "PC15_4") (pintype "bidirectional"))
    )
    (net (code "150") (name "unconnected-(U501E-PD2-Pad54)") (class "Default")
      (node (ref "U501") (pin "54") (pinfunction "PD2_54") (pintype "bidirectional"))
    )
    (net (code "151") (name "unconnected-(U501F-PA11-Pad44)") (class "Default")
      (node (ref "U501") (pin "44") (pinfunction "PA11_44") (pintype "bidirectional"))
    )
    (net (code "152") (name "unconnected-(U501H-PB12-Pad33)") (class "Default")
      (node (ref "U501") (pin "33") (pinfunction "PB12_33") (pintype "bidirectional"))
    )
    (net (code "153") (name "unconnected-(U702-CSET-Pad6)") (class "Default")
      (node (ref "U702") (pin "6") (pinfunction "CSET_6") (pintype "bidirectional"))
    )
    (net (code "154") (name "unconnected-(U702-POR2-Pad3)") (class "Default")
      (node (ref "U702") (pin "3") (pinfunction "POR2_3") (pintype "bidirectional"))
    )
    (net (code "155") (name "unconnected-(U702-VOUT2-Pad7)") (class "Default")
      (node (ref "U702") (pin "7") (pinfunction "VOUT2_7") (pintype "bidirectional"))
    )
    (net (code "156") (name "~{ACCEL_MAG_CS}") (class "Default")
      (node (ref "U101") (pin "P$15") (pinfunction "GPIO22_P$15") (pintype "bidirectional"))
      (node (ref "U302") (pin "8") (pinfunction "CS_8") (pintype "bidirectional"))
    )
    (net (code "157") (name "~{BARO_CS}") (class "Default")
      (node (ref "U101") (pin "P$16") (pinfunction "GPIO23_P$16") (pintype "bidirectional"))
      (node (ref "U304") (pin "5") (pinfunction "CSB2_5") (pintype "bidirectional"))
    )
    (net (code "158") (name "~{FRAM_CS}") (class "Default")
      (node (ref "U101") (pin "P$29") (pinfunction "GPIO5_P$29") (pintype "bidirectional"))
      (node (ref "U102") (pin "1") (pinfunction "~{S}_1") (pintype "bidirectional"))
    )
    (net (code "159") (name "~{GYRO_CS}") (class "Default")
      (node (ref "U101") (pin "P$32") (pinfunction "GPIO12_P$32") (pintype "bidirectional"))
      (node (ref "U301") (pin "5") (pinfunction "CS_5") (pintype "input"))
    )
    (net (code "160") (name "~{IO-LED_AMBER}") (class "Default")
      (node (ref "R409") (pin "P$1") (pinfunction "1_P$1") (pintype "passive"))
      (node (ref "U501") (pin "36") (pinfunction "PB15_36") (pintype "bidirectional"))
    )
    (net (code "161") (name "~{IO-LED_BLUE}") (class "Default")
      (node (ref "R410") (pin "P$1") (pinfunction "1_P$1") (pintype "passive"))
      (node (ref "U501") (pin "35") (pinfunction "PB14_35") (pintype "bidirectional"))
    )
    (net (code "162") (name "~{IO-LED_SAFETY}") (class "Default")
      (node (ref "R411") (pin "P$2") (pinfunction "2_P$2") (pintype "passive"))
      (node (ref "U501") (pin "34") (pinfunction "PB13_34") (pintype "bidirectional"))
    )
    (net (code "163") (name "~{MPU_CS}") (class "Default")
      (node (ref "U101") (pin "P$22") (pinfunction "GPIO25_P$22") (pintype "bidirectional"))
      (node (ref "U303") (pin "22") (pinfunction "~{CS}_22") (pintype "bidirectional"))
    )
    (net (code "164") (name "~{SBUS_OUTPUT_EN}") (class "Default")
      (node (ref "U501") (pin "37") (pinfunction "PC6_37") (pintype "bidirectional"))
      (node (ref "U601") (pin "7") (pinfunction "~{2OE}_7") (pintype "input"))
    )
  )
)
